# WideFeatherWing.net
KiCad netlist of a schematic drawn in EAGLE
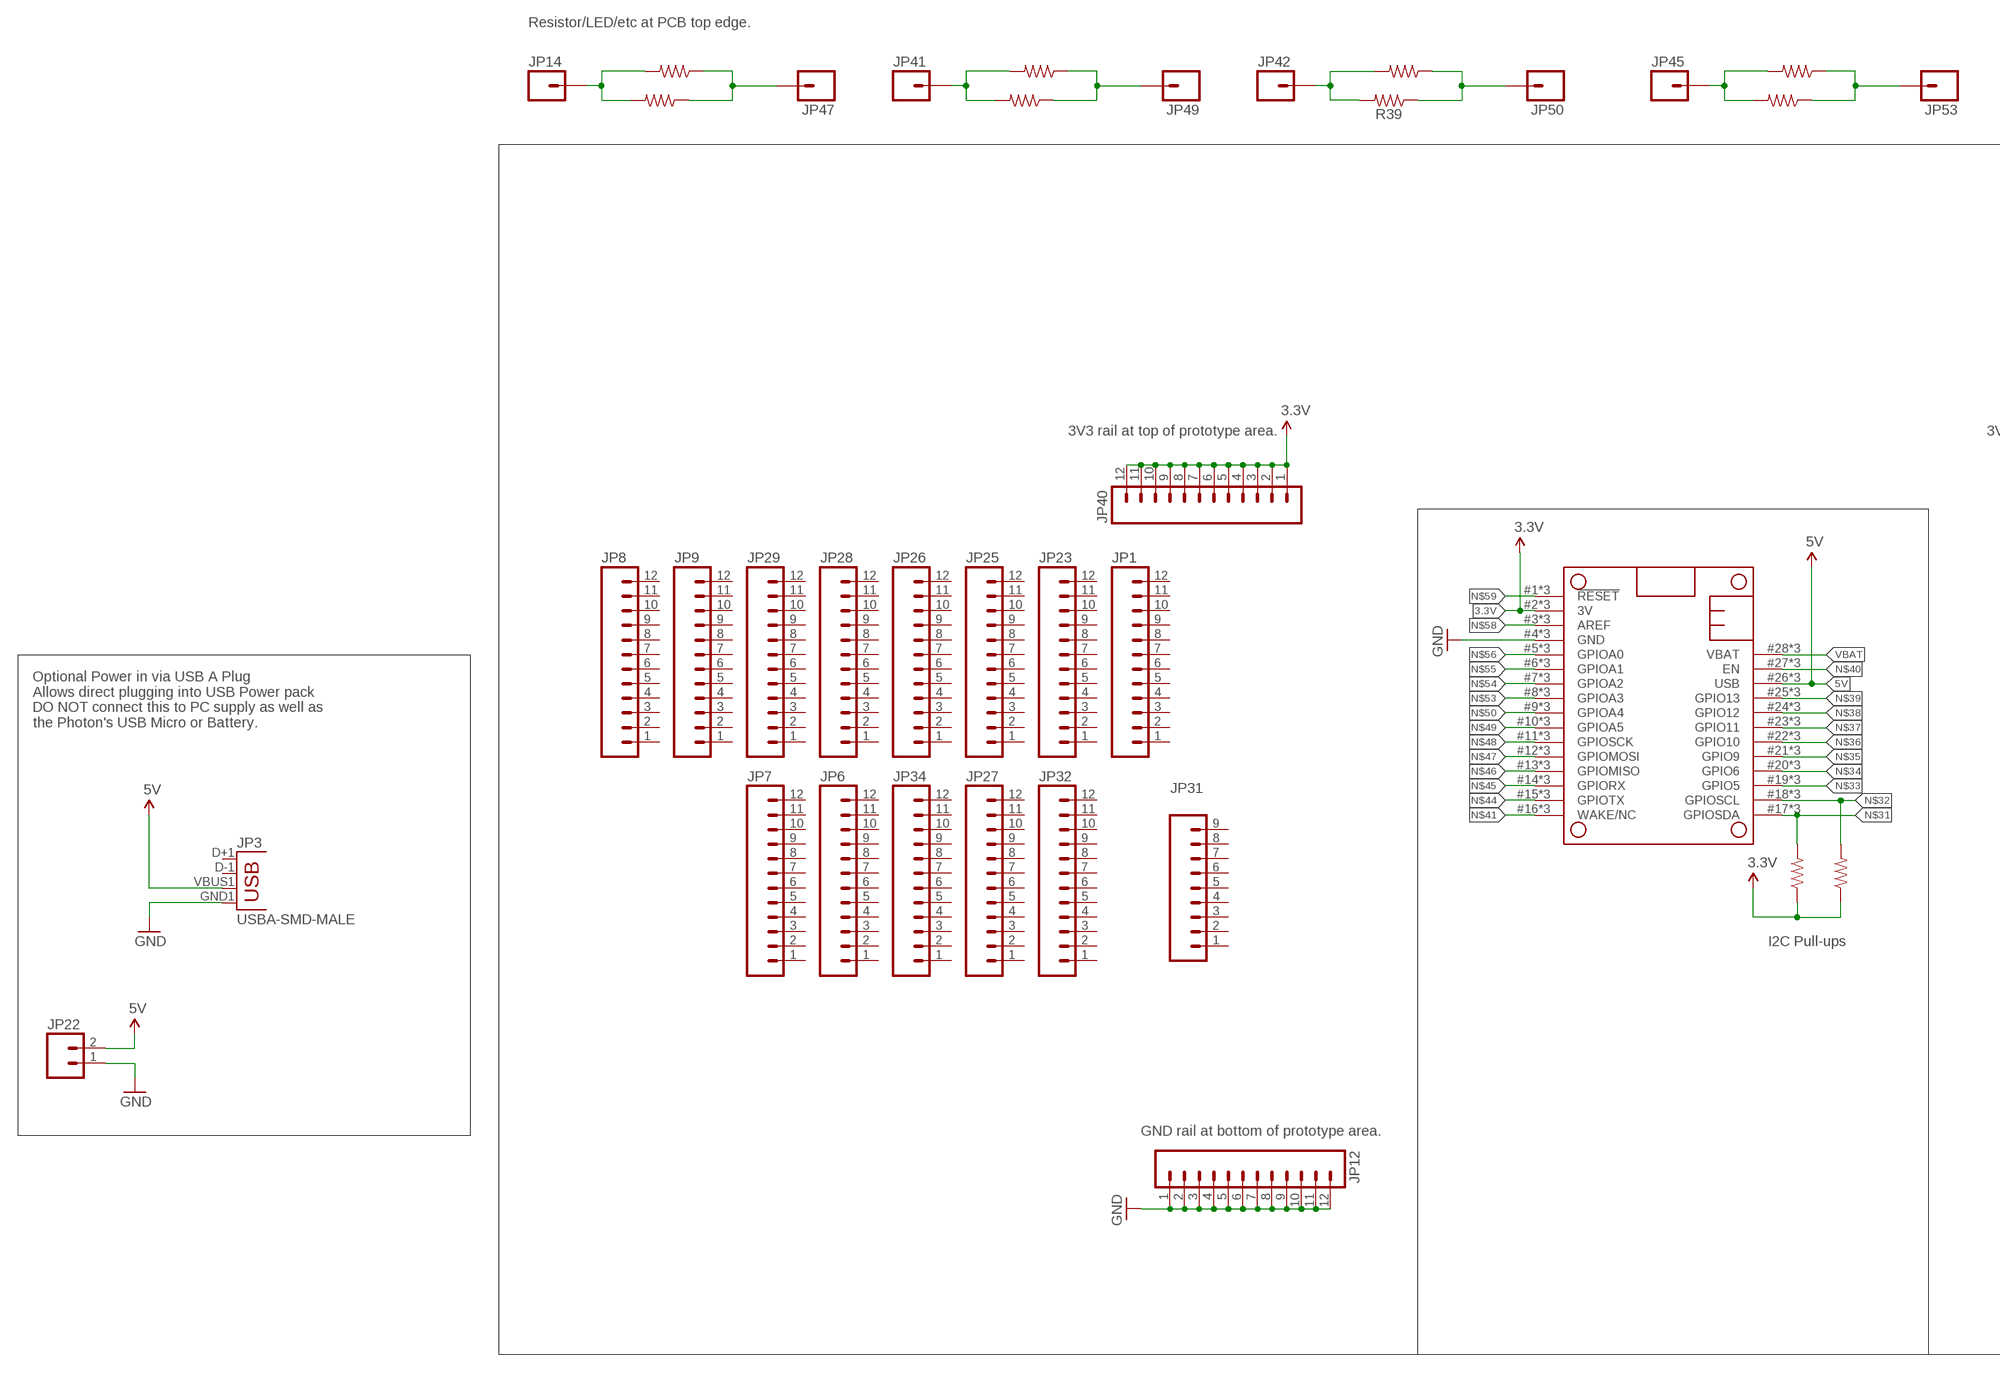
[diagram p0: schematic, sheet 1, part 1 of 2]
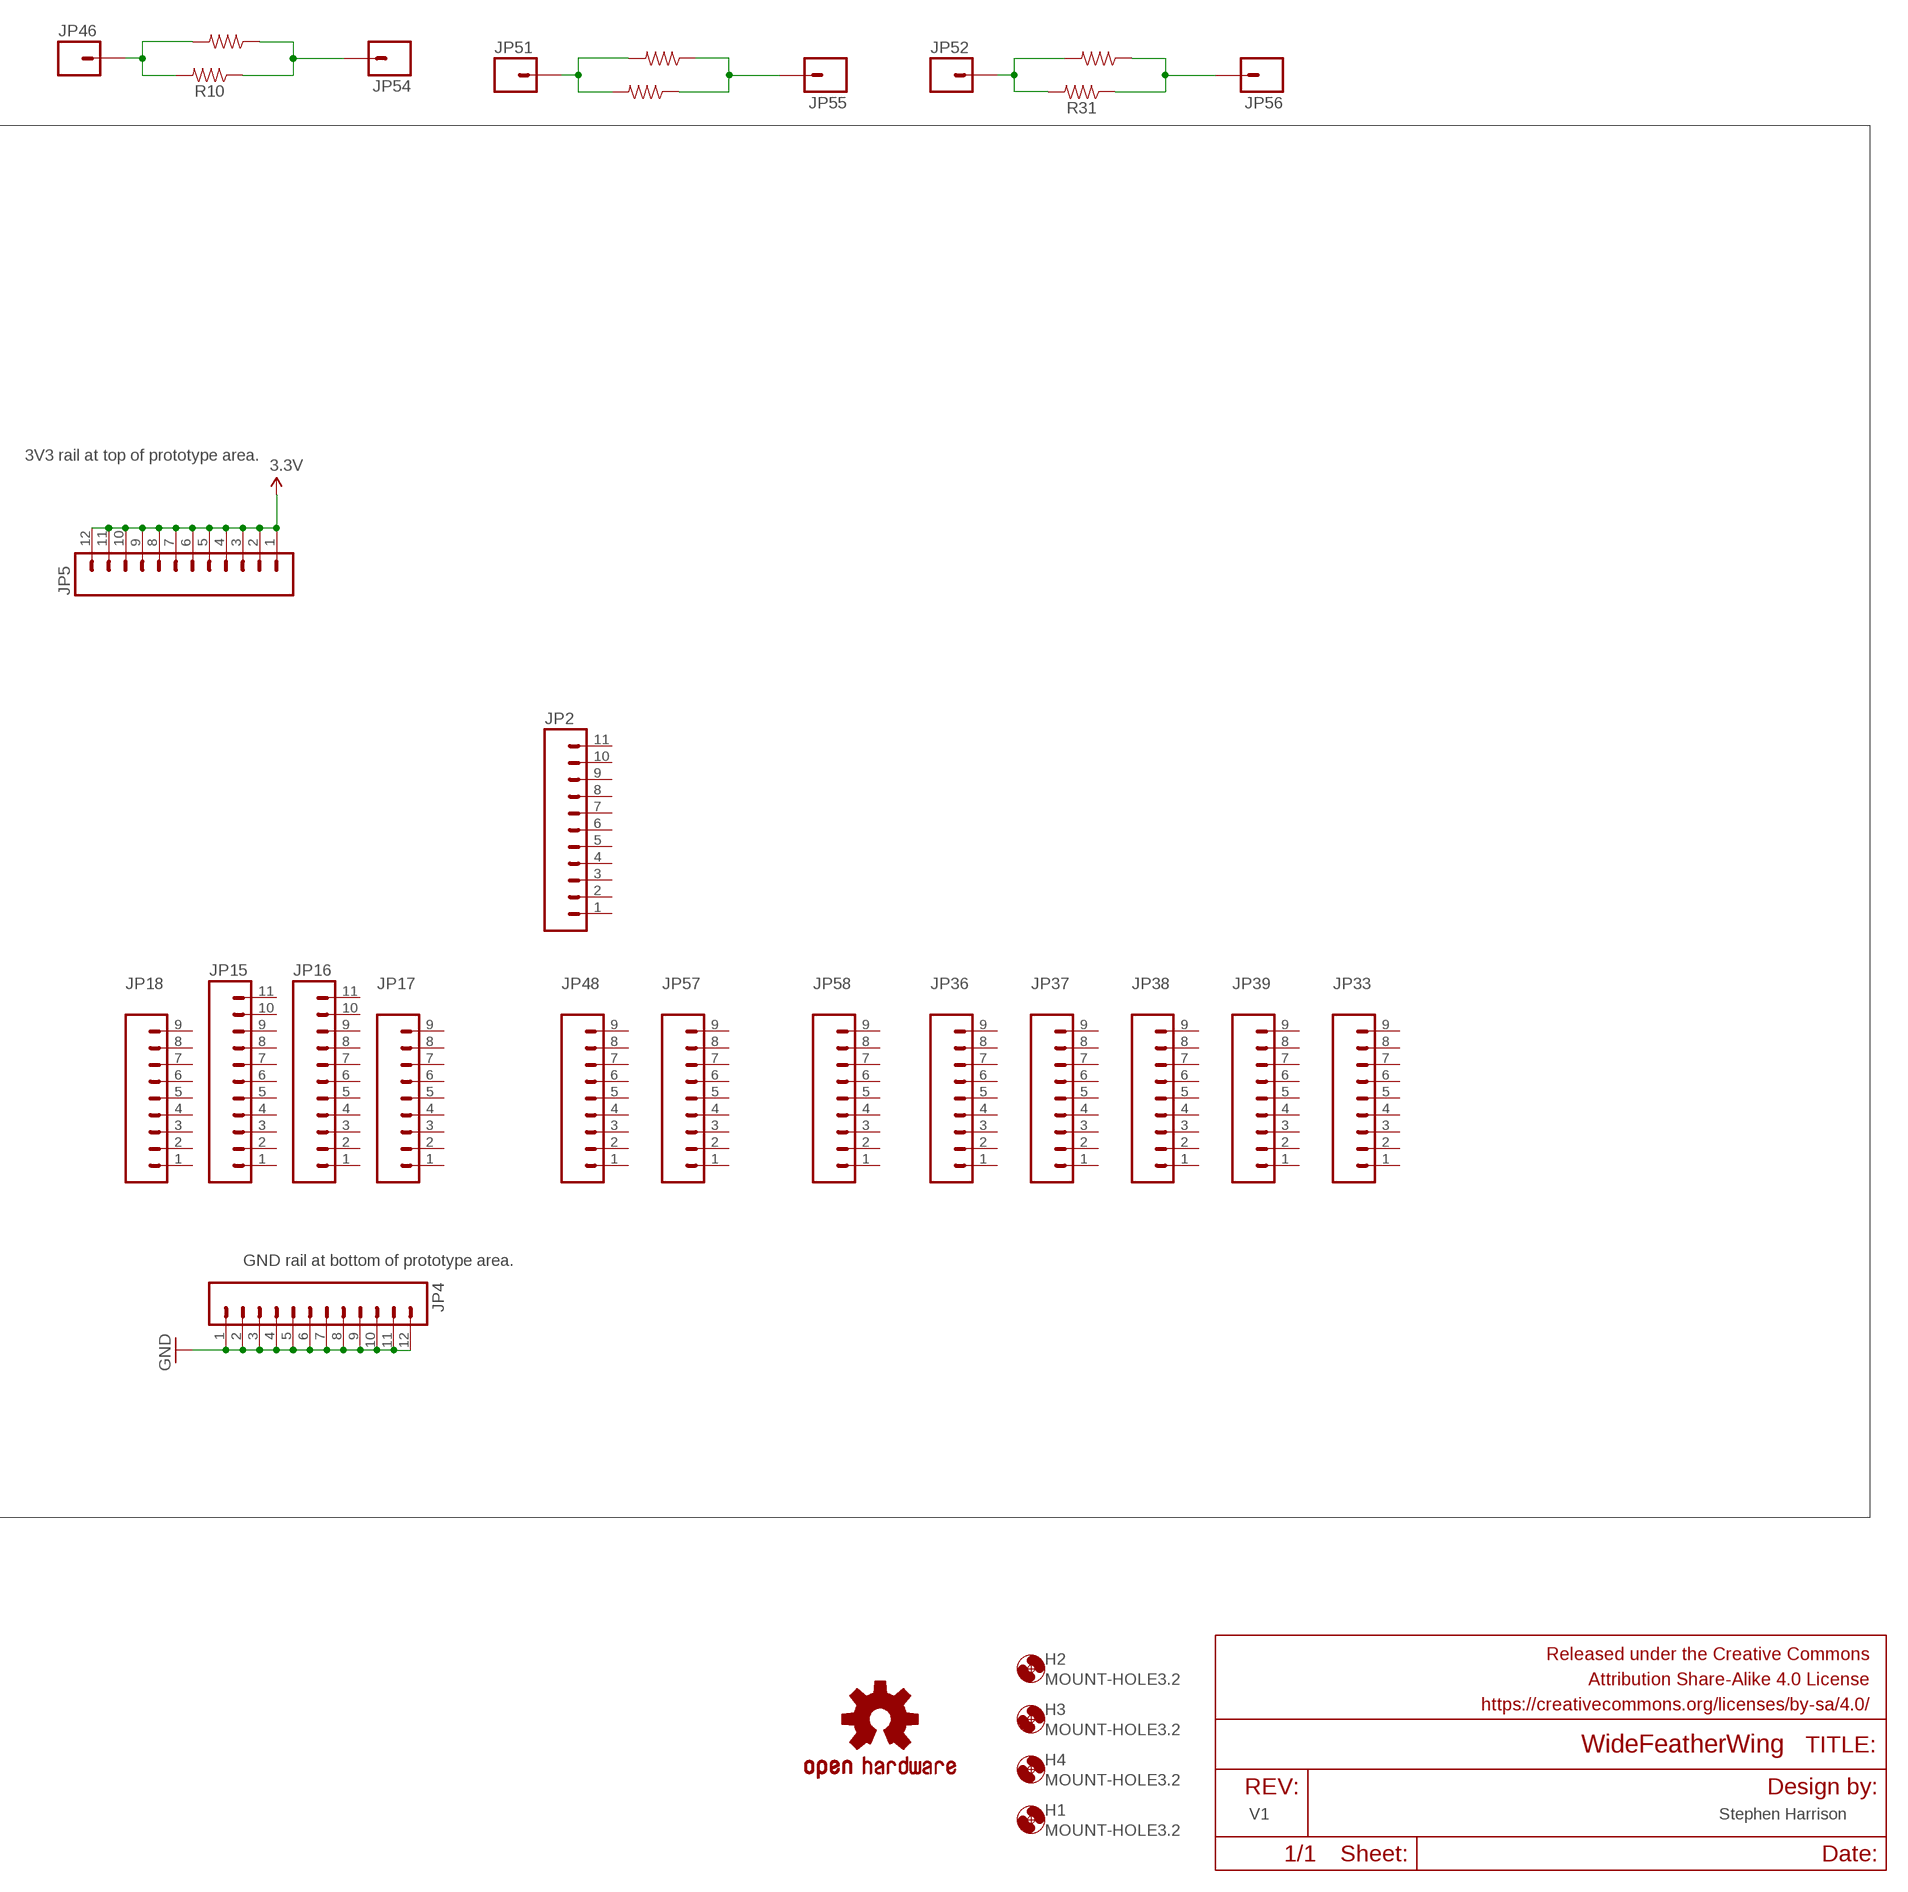
[diagram p1: schematic, sheet 1, part 2 of 2]

(export (version "E")
  (design (tool "Eeschema 10.0.6"))
  (components
    (comp (ref "FRAME1")
      (value "FRAME-LEDGER")
      (footprint "eagle-import:CREATIVE_COMMONS")
      (libsource (lib "eagle-import") (part "FRAME-LEDGER"))
    )
    (comp (ref "H1")
      (value "MOUNT-HOLE3.2")
      (footprint "eagle-import:3,2")
      (libsource (lib "eagle-import") (part "MOUNT-HOLE3.2"))
    )
    (comp (ref "H2")
      (value "MOUNT-HOLE3.2")
      (footprint "eagle-import:3,2")
      (libsource (lib "eagle-import") (part "MOUNT-HOLE3.2"))
    )
    (comp (ref "H3")
      (value "MOUNT-HOLE3.2")
      (footprint "eagle-import:3,2")
      (libsource (lib "eagle-import") (part "MOUNT-HOLE3.2"))
    )
    (comp (ref "H4")
      (value "MOUNT-HOLE3.2")
      (footprint "eagle-import:3,2")
      (libsource (lib "eagle-import") (part "MOUNT-HOLE3.2"))
    )
    (comp (ref "JP1")
      (value "M12NO_SILK")
      (footprint "eagle-import:1X12_NO_SILK")
      (libsource (lib "eagle-import") (part "M12NO_SILK"))
    )
    (comp (ref "JP2")
      (value "M111X11_NO_SILK")
      (footprint "eagle-import:1X11_NO_SILK")
      (libsource (lib "eagle-import") (part "M111X11_NO_SILK"))
    )
    (comp (ref "JP3")
      (value "USBA-SMD-MALE")
      (footprint "eagle-import:USB-A-SMT-MALE")
      (libsource (lib "eagle-import") (part "USBA-SMD-MALE"))
    )
    (comp (ref "JP4")
      (value "M12PTH")
      (footprint "eagle-import:1X12")
      (libsource (lib "eagle-import") (part "M12PTH"))
    )
    (comp (ref "JP5")
      (value "M12PTH")
      (footprint "eagle-import:1X12")
      (libsource (lib "eagle-import") (part "M12PTH"))
    )
    (comp (ref "JP6")
      (value "M12NO_SILK")
      (footprint "eagle-import:1X12_NO_SILK")
      (libsource (lib "eagle-import") (part "M12NO_SILK"))
    )
    (comp (ref "JP7")
      (value "M12NO_SILK")
      (footprint "eagle-import:1X12_NO_SILK")
      (libsource (lib "eagle-import") (part "M12NO_SILK"))
    )
    (comp (ref "JP8")
      (value "M12NO_SILK")
      (footprint "eagle-import:1X12_NO_SILK")
      (libsource (lib "eagle-import") (part "M12NO_SILK"))
    )
    (comp (ref "JP9")
      (value "M12NO_SILK")
      (footprint "eagle-import:1X12_NO_SILK")
      (libsource (lib "eagle-import") (part "M12NO_SILK"))
    )
    (comp (ref "JP12")
      (value "M12PTH")
      (footprint "eagle-import:1X12")
      (libsource (lib "eagle-import") (part "M12PTH"))
    )
    (comp (ref "JP14")
      (value "M01PTH")
      (footprint "eagle-import:1X01")
      (libsource (lib "eagle-import") (part "M01PTH"))
    )
    (comp (ref "JP15")
      (value "M111X11_NO_SILK")
      (footprint "eagle-import:1X11_NO_SILK")
      (libsource (lib "eagle-import") (part "M111X11_NO_SILK"))
    )
    (comp (ref "JP16")
      (value "M111X11_NO_SILK")
      (footprint "eagle-import:1X11_NO_SILK")
      (libsource (lib "eagle-import") (part "M111X11_NO_SILK"))
    )
    (comp (ref "JP17")
      (value "M09NO_SILK")
      (footprint "eagle-import:1X09_NO_SILK")
      (libsource (lib "eagle-import") (part "M09NO_SILK"))
    )
    (comp (ref "JP18")
      (value "M09NO_SILK")
      (footprint "eagle-import:1X09_NO_SILK")
      (libsource (lib "eagle-import") (part "M09NO_SILK"))
    )
    (comp (ref "JP22")
      (value "M021X02_NO_SILK")
      (footprint "eagle-import:1X02_NO_SILK")
      (libsource (lib "eagle-import") (part "M021X02_NO_SILK"))
    )
    (comp (ref "JP23")
      (value "M12NO_SILK")
      (footprint "eagle-import:1X12_NO_SILK")
      (libsource (lib "eagle-import") (part "M12NO_SILK"))
    )
    (comp (ref "JP25")
      (value "M12NO_SILK")
      (footprint "eagle-import:1X12_NO_SILK")
      (libsource (lib "eagle-import") (part "M12NO_SILK"))
    )
    (comp (ref "JP26")
      (value "M12NO_SILK")
      (footprint "eagle-import:1X12_NO_SILK")
      (libsource (lib "eagle-import") (part "M12NO_SILK"))
    )
    (comp (ref "JP27")
      (value "M12NO_SILK")
      (footprint "eagle-import:1X12_NO_SILK")
      (libsource (lib "eagle-import") (part "M12NO_SILK"))
    )
    (comp (ref "JP28")
      (value "M12NO_SILK")
      (footprint "eagle-import:1X12_NO_SILK")
      (libsource (lib "eagle-import") (part "M12NO_SILK"))
    )
    (comp (ref "JP29")
      (value "M12NO_SILK")
      (footprint "eagle-import:1X12_NO_SILK")
      (libsource (lib "eagle-import") (part "M12NO_SILK"))
    )
    (comp (ref "JP31")
      (value "M09NO_SILK")
      (footprint "eagle-import:1X09_NO_SILK")
      (libsource (lib "eagle-import") (part "M09NO_SILK"))
    )
    (comp (ref "JP32")
      (value "M12NO_SILK")
      (footprint "eagle-import:1X12_NO_SILK")
      (libsource (lib "eagle-import") (part "M12NO_SILK"))
    )
    (comp (ref "JP33")
      (value "M09NO_SILK")
      (footprint "eagle-import:1X09_NO_SILK")
      (libsource (lib "eagle-import") (part "M09NO_SILK"))
    )
    (comp (ref "JP34")
      (value "M12NO_SILK")
      (footprint "eagle-import:1X12_NO_SILK")
      (libsource (lib "eagle-import") (part "M12NO_SILK"))
    )
    (comp (ref "JP36")
      (value "M09NO_SILK")
      (footprint "eagle-import:1X09_NO_SILK")
      (libsource (lib "eagle-import") (part "M09NO_SILK"))
    )
    (comp (ref "JP37")
      (value "M09NO_SILK")
      (footprint "eagle-import:1X09_NO_SILK")
      (libsource (lib "eagle-import") (part "M09NO_SILK"))
    )
    (comp (ref "JP38")
      (value "M09NO_SILK")
      (footprint "eagle-import:1X09_NO_SILK")
      (libsource (lib "eagle-import") (part "M09NO_SILK"))
    )
    (comp (ref "JP39")
      (value "M09NO_SILK")
      (footprint "eagle-import:1X09_NO_SILK")
      (libsource (lib "eagle-import") (part "M09NO_SILK"))
    )
    (comp (ref "JP40")
      (value "M12PTH")
      (footprint "eagle-import:1X12")
      (libsource (lib "eagle-import") (part "M12PTH"))
    )
    (comp (ref "JP41")
      (value "M01PTH")
      (footprint "eagle-import:1X01")
      (libsource (lib "eagle-import") (part "M01PTH"))
    )
    (comp (ref "JP42")
      (value "M01PTH")
      (footprint "eagle-import:1X01")
      (libsource (lib "eagle-import") (part "M01PTH"))
    )
    (comp (ref "JP45")
      (value "M01PTH")
      (footprint "eagle-import:1X01")
      (libsource (lib "eagle-import") (part "M01PTH"))
    )
    (comp (ref "JP46")
      (value "M01PTH")
      (footprint "eagle-import:1X01")
      (libsource (lib "eagle-import") (part "M01PTH"))
    )
    (comp (ref "JP47")
      (value "M01PTH")
      (footprint "eagle-import:1X01")
      (libsource (lib "eagle-import") (part "M01PTH"))
    )
    (comp (ref "JP48")
      (value "M09NO_SILK")
      (footprint "eagle-import:1X09_NO_SILK")
      (libsource (lib "eagle-import") (part "M09NO_SILK"))
    )
    (comp (ref "JP49")
      (value "M01PTH")
      (footprint "eagle-import:1X01")
      (libsource (lib "eagle-import") (part "M01PTH"))
    )
    (comp (ref "JP50")
      (value "M01PTH")
      (footprint "eagle-import:1X01")
      (libsource (lib "eagle-import") (part "M01PTH"))
    )
    (comp (ref "JP51")
      (value "M01PTH")
      (footprint "eagle-import:1X01")
      (libsource (lib "eagle-import") (part "M01PTH"))
    )
    (comp (ref "JP52")
      (value "M01PTH")
      (footprint "eagle-import:1X01")
      (libsource (lib "eagle-import") (part "M01PTH"))
    )
    (comp (ref "JP53")
      (value "M01PTH")
      (footprint "eagle-import:1X01")
      (libsource (lib "eagle-import") (part "M01PTH"))
    )
    (comp (ref "JP54")
      (value "M01PTH")
      (footprint "eagle-import:1X01")
      (libsource (lib "eagle-import") (part "M01PTH"))
    )
    (comp (ref "JP55")
      (value "M01PTH")
      (footprint "eagle-import:1X01")
      (libsource (lib "eagle-import") (part "M01PTH"))
    )
    (comp (ref "JP56")
      (value "M01PTH")
      (footprint "eagle-import:1X01")
      (libsource (lib "eagle-import") (part "M01PTH"))
    )
    (comp (ref "JP57")
      (value "M09NO_SILK")
      (footprint "eagle-import:1X09_NO_SILK")
      (libsource (lib "eagle-import") (part "M09NO_SILK"))
    )
    (comp (ref "JP58")
      (value "M09NO_SILK")
      (footprint "eagle-import:1X09_NO_SILK")
      (libsource (lib "eagle-import") (part "M09NO_SILK"))
    )
    (comp (ref "LOGO1")
      (value "OSHW-LOGOM")
      (footprint "eagle-import:OSHW-LOGO-M")
      (libsource (lib "eagle-import") (part "OSHW-LOGOM"))
    )
    (comp (ref "MS1")
      (value "FEATHERWINGFEATHEWING_BREAKOUT")
      (footprint "eagle-import:FEATHERWING_BREAKOUT")
      (libsource (lib "eagle-import") (part "FEATHERWINGFEATHEWING_BREAKOUT"))
    )
    (comp (ref "R5")
      (value "RESISTOR1206")
      (footprint "eagle-import:1206")
      (libsource (lib "eagle-import") (part "RESISTOR1206"))
    )
    (comp (ref "R9")
      (value "RESISTOR1206")
      (footprint "eagle-import:1206")
      (libsource (lib "eagle-import") (part "RESISTOR1206"))
    )
    (comp (ref "R10")
      (value "RESISTOR1206")
      (footprint "eagle-import:1206")
      (libsource (lib "eagle-import") (part "RESISTOR1206"))
    )
    (comp (ref "R17")
      (value "RESISTOR1206")
      (footprint "eagle-import:1206")
      (libsource (lib "eagle-import") (part "RESISTOR1206"))
    )
    (comp (ref "R24")
      (value "RESISTOR1206")
      (footprint "eagle-import:1206")
      (libsource (lib "eagle-import") (part "RESISTOR1206"))
    )
    (comp (ref "R30")
      (value "RESISTOR1206")
      (footprint "eagle-import:1206")
      (libsource (lib "eagle-import") (part "RESISTOR1206"))
    )
    (comp (ref "R31")
      (value "RESISTOR1206")
      (footprint "eagle-import:1206")
      (libsource (lib "eagle-import") (part "RESISTOR1206"))
    )
    (comp (ref "R32")
      (value "RESISTOR1206")
      (footprint "eagle-import:1206")
      (libsource (lib "eagle-import") (part "RESISTOR1206"))
    )
    (comp (ref "R34")
      (value "RESISTOR1206")
      (footprint "eagle-import:1206")
      (libsource (lib "eagle-import") (part "RESISTOR1206"))
    )
    (comp (ref "R35")
      (value "RESISTOR1206")
      (footprint "eagle-import:1206")
      (libsource (lib "eagle-import") (part "RESISTOR1206"))
    )
    (comp (ref "R36")
      (value "RESISTOR1206")
      (footprint "eagle-import:1206")
      (libsource (lib "eagle-import") (part "RESISTOR1206"))
    )
    (comp (ref "R37")
      (value "RESISTOR1206")
      (footprint "eagle-import:1206")
      (libsource (lib "eagle-import") (part "RESISTOR1206"))
    )
    (comp (ref "R39")
      (value "RESISTOR1206")
      (footprint "eagle-import:1206")
      (libsource (lib "eagle-import") (part "RESISTOR1206"))
    )
    (comp (ref "R40")
      (value "RESISTOR1206")
      (footprint "eagle-import:1206")
      (libsource (lib "eagle-import") (part "RESISTOR1206"))
    )
    (comp (ref "R41")
      (value "RESISTOR1206")
      (footprint "eagle-import:1206")
      (libsource (lib "eagle-import") (part "RESISTOR1206"))
    )
    (comp (ref "R44")
      (value "RESISTOR1206")
      (footprint "eagle-import:1206")
      (libsource (lib "eagle-import") (part "RESISTOR1206"))
    )
  )
  (nets
    (net (code "1") (name "3.3V") (class "Default")
      (node (ref "JP40") (pin "1") (pinfunction "1_1") (pintype "passive"))
      (node (ref "JP40") (pin "10") (pinfunction "10_10") (pintype "passive"))
      (node (ref "JP40") (pin "11") (pinfunction "11_11") (pintype "passive"))
      (node (ref "JP40") (pin "12") (pinfunction "12_12") (pintype "passive"))
      (node (ref "JP40") (pin "2") (pinfunction "2_2") (pintype "passive"))
      (node (ref "JP40") (pin "3") (pinfunction "3_3") (pintype "passive"))
      (node (ref "JP40") (pin "4") (pinfunction "4_4") (pintype "passive"))
      (node (ref "JP40") (pin "5") (pinfunction "5_5") (pintype "passive"))
      (node (ref "JP40") (pin "6") (pinfunction "6_6") (pintype "passive"))
      (node (ref "JP40") (pin "7") (pinfunction "7_7") (pintype "passive"))
      (node (ref "JP40") (pin "8") (pinfunction "8_8") (pintype "passive"))
      (node (ref "JP40") (pin "9") (pinfunction "9_9") (pintype "passive"))
      (node (ref "JP5") (pin "1") (pinfunction "1_1") (pintype "passive"))
      (node (ref "JP5") (pin "10") (pinfunction "10_10") (pintype "passive"))
      (node (ref "JP5") (pin "11") (pinfunction "11_11") (pintype "passive"))
      (node (ref "JP5") (pin "12") (pinfunction "12_12") (pintype "passive"))
      (node (ref "JP5") (pin "2") (pinfunction "2_2") (pintype "passive"))
      (node (ref "JP5") (pin "3") (pinfunction "3_3") (pintype "passive"))
      (node (ref "JP5") (pin "4") (pinfunction "4_4") (pintype "passive"))
      (node (ref "JP5") (pin "5") (pinfunction "5_5") (pintype "passive"))
      (node (ref "JP5") (pin "6") (pinfunction "6_6") (pintype "passive"))
      (node (ref "JP5") (pin "7") (pinfunction "7_7") (pintype "passive"))
      (node (ref "JP5") (pin "8") (pinfunction "8_8") (pintype "passive"))
      (node (ref "JP5") (pin "9") (pinfunction "9_9") (pintype "passive"))
      (node (ref "MS1") (pin "#2") (pinfunction "3V_#2") (pintype "power_in"))
      (node (ref "MS1") (pin "2") (pinfunction "3V_2") (pintype "power_in"))
      (node (ref "MS1") (pin "@2") (pinfunction "3V_@2") (pintype "power_in"))
      (node (ref "R5") (pin "1") (pinfunction "1_1") (pintype "passive"))
      (node (ref "R9") (pin "1") (pinfunction "1_1") (pintype "passive"))
    )
    (net (code "2") (name "5V") (class "Default")
      (node (ref "JP22") (pin "2") (pinfunction "2_2") (pintype "passive"))
      (node (ref "JP3") (pin "VBUS1") (pinfunction "VBUS_VBUS1") (pintype "bidirectional"))
      (node (ref "MS1") (pin "#26") (pinfunction "USB_#26") (pintype "power_in"))
      (node (ref "MS1") (pin "26") (pinfunction "USB_26") (pintype "power_in"))
      (node (ref "MS1") (pin "@26") (pinfunction "USB_@26") (pintype "power_in"))
    )
    (net (code "3") (name "GND") (class "Default")
      (node (ref "JP12") (pin "1") (pinfunction "1_1") (pintype "passive"))
      (node (ref "JP12") (pin "10") (pinfunction "10_10") (pintype "passive"))
      (node (ref "JP12") (pin "11") (pinfunction "11_11") (pintype "passive"))
      (node (ref "JP12") (pin "12") (pinfunction "12_12") (pintype "passive"))
      (node (ref "JP12") (pin "2") (pinfunction "2_2") (pintype "passive"))
      (node (ref "JP12") (pin "3") (pinfunction "3_3") (pintype "passive"))
      (node (ref "JP12") (pin "4") (pinfunction "4_4") (pintype "passive"))
      (node (ref "JP12") (pin "5") (pinfunction "5_5") (pintype "passive"))
      (node (ref "JP12") (pin "6") (pinfunction "6_6") (pintype "passive"))
      (node (ref "JP12") (pin "7") (pinfunction "7_7") (pintype "passive"))
      (node (ref "JP12") (pin "8") (pinfunction "8_8") (pintype "passive"))
      (node (ref "JP12") (pin "9") (pinfunction "9_9") (pintype "passive"))
      (node (ref "JP22") (pin "1") (pinfunction "1_1") (pintype "passive"))
      (node (ref "JP3") (pin "GND1") (pinfunction "GND_GND1") (pintype "bidirectional"))
      (node (ref "JP4") (pin "1") (pinfunction "1_1") (pintype "passive"))
      (node (ref "JP4") (pin "10") (pinfunction "10_10") (pintype "passive"))
      (node (ref "JP4") (pin "11") (pinfunction "11_11") (pintype "passive"))
      (node (ref "JP4") (pin "12") (pinfunction "12_12") (pintype "passive"))
      (node (ref "JP4") (pin "2") (pinfunction "2_2") (pintype "passive"))
      (node (ref "JP4") (pin "3") (pinfunction "3_3") (pintype "passive"))
      (node (ref "JP4") (pin "4") (pinfunction "4_4") (pintype "passive"))
      (node (ref "JP4") (pin "5") (pinfunction "5_5") (pintype "passive"))
      (node (ref "JP4") (pin "6") (pinfunction "6_6") (pintype "passive"))
      (node (ref "JP4") (pin "7") (pinfunction "7_7") (pintype "passive"))
      (node (ref "JP4") (pin "8") (pinfunction "8_8") (pintype "passive"))
      (node (ref "JP4") (pin "9") (pinfunction "9_9") (pintype "passive"))
      (node (ref "MS1") (pin "#4") (pinfunction "GND_#4") (pintype "power_in"))
      (node (ref "MS1") (pin "4") (pinfunction "GND_4") (pintype "power_in"))
      (node (ref "MS1") (pin "@4") (pinfunction "GND_@4") (pintype "power_in"))
    )
    (net (code "4") (name "N$31") (class "Default")
      (node (ref "MS1") (pin "#17") (pinfunction "GPIOSDA_#17") (pintype "bidirectional"))
      (node (ref "MS1") (pin "17") (pinfunction "GPIOSDA_17") (pintype "bidirectional"))
      (node (ref "MS1") (pin "@17") (pinfunction "GPIOSDA_@17") (pintype "bidirectional"))
      (node (ref "R5") (pin "2") (pinfunction "2_2") (pintype "passive"))
    )
    (net (code "5") (name "N$32") (class "Default")
      (node (ref "MS1") (pin "#18") (pinfunction "GPIOSCL_#18") (pintype "bidirectional"))
      (node (ref "MS1") (pin "18") (pinfunction "GPIOSCL_18") (pintype "bidirectional"))
      (node (ref "MS1") (pin "@!8") (pinfunction "GPIOSCL_@!8") (pintype "bidirectional"))
      (node (ref "R9") (pin "2") (pinfunction "2_2") (pintype "passive"))
    )
    (net (code "6") (name "N$33") (class "Default")
      (node (ref "MS1") (pin "#19") (pinfunction "GPIO5_#19") (pintype "bidirectional"))
      (node (ref "MS1") (pin "19") (pinfunction "GPIO5_19") (pintype "bidirectional"))
      (node (ref "MS1") (pin "@19") (pinfunction "GPIO5_@19") (pintype "bidirectional"))
    )
    (net (code "7") (name "N$34") (class "Default")
      (node (ref "MS1") (pin "#20") (pinfunction "GPIO6_#20") (pintype "bidirectional"))
      (node (ref "MS1") (pin "20") (pinfunction "GPIO6_20") (pintype "bidirectional"))
      (node (ref "MS1") (pin "@20") (pinfunction "GPIO6_@20") (pintype "bidirectional"))
    )
    (net (code "8") (name "N$35") (class "Default")
      (node (ref "MS1") (pin "#21") (pinfunction "GPIO9_#21") (pintype "bidirectional"))
      (node (ref "MS1") (pin "21") (pinfunction "GPIO9_21") (pintype "bidirectional"))
      (node (ref "MS1") (pin "@21") (pinfunction "GPIO9_@21") (pintype "bidirectional"))
    )
    (net (code "9") (name "N$36") (class "Default")
      (node (ref "MS1") (pin "#22") (pinfunction "GPIO10_#22") (pintype "bidirectional"))
      (node (ref "MS1") (pin "22") (pinfunction "GPIO10_22") (pintype "bidirectional"))
      (node (ref "MS1") (pin "@22") (pinfunction "GPIO10_@22") (pintype "bidirectional"))
    )
    (net (code "10") (name "N$37") (class "Default")
      (node (ref "MS1") (pin "#23") (pinfunction "GPIO11_#23") (pintype "bidirectional"))
      (node (ref "MS1") (pin "23") (pinfunction "GPIO11_23") (pintype "bidirectional"))
      (node (ref "MS1") (pin "@23") (pinfunction "GPIO11_@23") (pintype "bidirectional"))
    )
    (net (code "11") (name "N$38") (class "Default")
      (node (ref "MS1") (pin "#24") (pinfunction "GPIO12_#24") (pintype "bidirectional"))
      (node (ref "MS1") (pin "24") (pinfunction "GPIO12_24") (pintype "bidirectional"))
      (node (ref "MS1") (pin "@24") (pinfunction "GPIO12_@24") (pintype "bidirectional"))
    )
    (net (code "12") (name "N$39") (class "Default")
      (node (ref "MS1") (pin "#25") (pinfunction "GPIO13_#25") (pintype "bidirectional"))
      (node (ref "MS1") (pin "25") (pinfunction "GPIO13_25") (pintype "bidirectional"))
      (node (ref "MS1") (pin "@25") (pinfunction "GPIO13_@25") (pintype "bidirectional"))
    )
    (net (code "13") (name "N$40") (class "Default")
      (node (ref "MS1") (pin "#27") (pinfunction "EN_#27") (pintype "passive"))
      (node (ref "MS1") (pin "27") (pinfunction "EN_27") (pintype "passive"))
      (node (ref "MS1") (pin "@27") (pinfunction "EN_@27") (pintype "passive"))
    )
    (net (code "14") (name "N$41") (class "Default")
      (node (ref "MS1") (pin "#16") (pinfunction "WAKE/NC_#16") (pintype "passive"))
      (node (ref "MS1") (pin "16") (pinfunction "WAKE/NC_16") (pintype "passive"))
      (node (ref "MS1") (pin "@16") (pinfunction "WAKE/NC_@16") (pintype "passive"))
    )
    (net (code "15") (name "N$44") (class "Default")
      (node (ref "MS1") (pin "#15") (pinfunction "GPIOTX_#15") (pintype "bidirectional"))
      (node (ref "MS1") (pin "15") (pinfunction "GPIOTX_15") (pintype "bidirectional"))
      (node (ref "MS1") (pin "@15") (pinfunction "GPIOTX_@15") (pintype "bidirectional"))
    )
    (net (code "16") (name "N$45") (class "Default")
      (node (ref "MS1") (pin "#14") (pinfunction "GPIORX_#14") (pintype "bidirectional"))
      (node (ref "MS1") (pin "14") (pinfunction "GPIORX_14") (pintype "bidirectional"))
      (node (ref "MS1") (pin "@14") (pinfunction "GPIORX_@14") (pintype "bidirectional"))
    )
    (net (code "17") (name "N$46") (class "Default")
      (node (ref "MS1") (pin "#13") (pinfunction "GPIOMISO_#13") (pintype "bidirectional"))
      (node (ref "MS1") (pin "13") (pinfunction "GPIOMISO_13") (pintype "bidirectional"))
      (node (ref "MS1") (pin "@13") (pinfunction "GPIOMISO_@13") (pintype "bidirectional"))
    )
    (net (code "18") (name "N$47") (class "Default")
      (node (ref "MS1") (pin "#12") (pinfunction "GPIOMOSI_#12") (pintype "bidirectional"))
      (node (ref "MS1") (pin "12") (pinfunction "GPIOMOSI_12") (pintype "bidirectional"))
      (node (ref "MS1") (pin "@12") (pinfunction "GPIOMOSI_@12") (pintype "bidirectional"))
    )
    (net (code "19") (name "N$48") (class "Default")
      (node (ref "MS1") (pin "#11") (pinfunction "GPIOSCK_#11") (pintype "bidirectional"))
      (node (ref "MS1") (pin "11") (pinfunction "GPIOSCK_11") (pintype "bidirectional"))
      (node (ref "MS1") (pin "@11") (pinfunction "GPIOSCK_@11") (pintype "bidirectional"))
    )
    (net (code "20") (name "N$49") (class "Default")
      (node (ref "MS1") (pin "#10") (pinfunction "GPIOA5_#10") (pintype "bidirectional"))
      (node (ref "MS1") (pin "10") (pinfunction "GPIOA5_10") (pintype "bidirectional"))
      (node (ref "MS1") (pin "@10") (pinfunction "GPIOA5_@10") (pintype "bidirectional"))
    )
    (net (code "21") (name "N$50") (class "Default")
      (node (ref "MS1") (pin "#9") (pinfunction "GPIOA4_#9") (pintype "bidirectional"))
      (node (ref "MS1") (pin "9") (pinfunction "GPIOA4_9") (pintype "bidirectional"))
      (node (ref "MS1") (pin "@9") (pinfunction "GPIOA4_@9") (pintype "bidirectional"))
    )
    (net (code "22") (name "N$53") (class "Default")
      (node (ref "MS1") (pin "#8") (pinfunction "GPIOA3_#8") (pintype "bidirectional"))
      (node (ref "MS1") (pin "8") (pinfunction "GPIOA3_8") (pintype "bidirectional"))
      (node (ref "MS1") (pin "@8") (pinfunction "GPIOA3_@8") (pintype "bidirectional"))
    )
    (net (code "23") (name "N$54") (class "Default")
      (node (ref "MS1") (pin "#7") (pinfunction "GPIOA2_#7") (pintype "bidirectional"))
      (node (ref "MS1") (pin "7") (pinfunction "GPIOA2_7") (pintype "bidirectional"))
      (node (ref "MS1") (pin "@7") (pinfunction "GPIOA2_@7") (pintype "bidirectional"))
    )
    (net (code "24") (name "N$55") (class "Default")
      (node (ref "MS1") (pin "#6") (pinfunction "GPIOA1_#6") (pintype "bidirectional"))
      (node (ref "MS1") (pin "6") (pinfunction "GPIOA1_6") (pintype "bidirectional"))
      (node (ref "MS1") (pin "@6") (pinfunction "GPIOA1_@6") (pintype "bidirectional"))
    )
    (net (code "25") (name "N$56") (class "Default")
      (node (ref "MS1") (pin "#5") (pinfunction "GPIOA0_#5") (pintype "bidirectional"))
      (node (ref "MS1") (pin "5") (pinfunction "GPIOA0_5") (pintype "bidirectional"))
      (node (ref "MS1") (pin "@5") (pinfunction "GPIOA0_@5") (pintype "bidirectional"))
    )
    (net (code "26") (name "N$58") (class "Default")
      (node (ref "MS1") (pin "#3") (pinfunction "AREF_#3") (pintype "passive"))
      (node (ref "MS1") (pin "3") (pinfunction "AREF_3") (pintype "passive"))
      (node (ref "MS1") (pin "@3") (pinfunction "AREF_@3") (pintype "passive"))
    )
    (net (code "27") (name "N$59") (class "Default")
      (node (ref "MS1") (pin "#1") (pinfunction "~{RESET}_#1") (pintype "input"))
      (node (ref "MS1") (pin "1") (pinfunction "~{RESET}_1") (pintype "input"))
      (node (ref "MS1") (pin "@1") (pinfunction "~{RESET}_@1") (pintype "input"))
    )
    (net (code "28") (name "Net-(JP14-Pad1)") (class "Default")
      (node (ref "JP14") (pin "1") (pinfunction "1_1") (pintype "passive"))
      (node (ref "R34") (pin "2") (pinfunction "2_2") (pintype "passive"))
      (node (ref "R35") (pin "2") (pinfunction "2_2") (pintype "passive"))
    )
    (net (code "29") (name "Net-(JP41-Pad1)") (class "Default")
      (node (ref "JP41") (pin "1") (pinfunction "1_1") (pintype "passive"))
      (node (ref "R40") (pin "2") (pinfunction "2_2") (pintype "passive"))
      (node (ref "R41") (pin "2") (pinfunction "2_2") (pintype "passive"))
    )
    (net (code "30") (name "Net-(JP42-Pad1)") (class "Default")
      (node (ref "JP42") (pin "1") (pinfunction "1_1") (pintype "passive"))
      (node (ref "R39") (pin "2") (pinfunction "2_2") (pintype "passive"))
      (node (ref "R44") (pin "2") (pinfunction "2_2") (pintype "passive"))
    )
    (net (code "31") (name "Net-(JP45-Pad1)") (class "Default")
      (node (ref "JP45") (pin "1") (pinfunction "1_1") (pintype "passive"))
      (node (ref "R17") (pin "2") (pinfunction "2_2") (pintype "passive"))
      (node (ref "R24") (pin "2") (pinfunction "2_2") (pintype "passive"))
    )
    (net (code "32") (name "Net-(JP46-Pad1)") (class "Default")
      (node (ref "JP46") (pin "1") (pinfunction "1_1") (pintype "passive"))
      (node (ref "R10") (pin "2") (pinfunction "2_2") (pintype "passive"))
      (node (ref "R30") (pin "2") (pinfunction "2_2") (pintype "passive"))
    )
    (net (code "33") (name "Net-(JP47-Pad1)") (class "Default")
      (node (ref "JP47") (pin "1") (pinfunction "1_1") (pintype "passive"))
      (node (ref "R34") (pin "1") (pinfunction "1_1") (pintype "passive"))
      (node (ref "R35") (pin "1") (pinfunction "1_1") (pintype "passive"))
    )
    (net (code "34") (name "Net-(JP49-Pad1)") (class "Default")
      (node (ref "JP49") (pin "1") (pinfunction "1_1") (pintype "passive"))
      (node (ref "R40") (pin "1") (pinfunction "1_1") (pintype "passive"))
      (node (ref "R41") (pin "1") (pinfunction "1_1") (pintype "passive"))
    )
    (net (code "35") (name "Net-(JP50-Pad1)") (class "Default")
      (node (ref "JP50") (pin "1") (pinfunction "1_1") (pintype "passive"))
      (node (ref "R39") (pin "1") (pinfunction "1_1") (pintype "passive"))
      (node (ref "R44") (pin "1") (pinfunction "1_1") (pintype "passive"))
    )
    (net (code "36") (name "Net-(JP51-Pad1)") (class "Default")
      (node (ref "JP51") (pin "1") (pinfunction "1_1") (pintype "passive"))
      (node (ref "R32") (pin "2") (pinfunction "2_2") (pintype "passive"))
      (node (ref "R36") (pin "2") (pinfunction "2_2") (pintype "passive"))
    )
    (net (code "37") (name "Net-(JP52-Pad1)") (class "Default")
      (node (ref "JP52") (pin "1") (pinfunction "1_1") (pintype "passive"))
      (node (ref "R31") (pin "2") (pinfunction "2_2") (pintype "passive"))
      (node (ref "R37") (pin "2") (pinfunction "2_2") (pintype "passive"))
    )
    (net (code "38") (name "Net-(JP53-Pad1)") (class "Default")
      (node (ref "JP53") (pin "1") (pinfunction "1_1") (pintype "passive"))
      (node (ref "R17") (pin "1") (pinfunction "1_1") (pintype "passive"))
      (node (ref "R24") (pin "1") (pinfunction "1_1") (pintype "passive"))
    )
    (net (code "39") (name "Net-(JP54-Pad1)") (class "Default")
      (node (ref "JP54") (pin "1") (pinfunction "1_1") (pintype "passive"))
      (node (ref "R10") (pin "1") (pinfunction "1_1") (pintype "passive"))
      (node (ref "R30") (pin "1") (pinfunction "1_1") (pintype "passive"))
    )
    (net (code "40") (name "Net-(JP55-Pad1)") (class "Default")
      (node (ref "JP55") (pin "1") (pinfunction "1_1") (pintype "passive"))
      (node (ref "R32") (pin "1") (pinfunction "1_1") (pintype "passive"))
      (node (ref "R36") (pin "1") (pinfunction "1_1") (pintype "passive"))
    )
    (net (code "41") (name "Net-(JP56-Pad1)") (class "Default")
      (node (ref "JP56") (pin "1") (pinfunction "1_1") (pintype "passive"))
      (node (ref "R31") (pin "1") (pinfunction "1_1") (pintype "passive"))
      (node (ref "R37") (pin "1") (pinfunction "1_1") (pintype "passive"))
    )
    (net (code "42") (name "VBAT") (class "Default")
      (node (ref "MS1") (pin "#28") (pinfunction "VBAT_#28") (pintype "power_in"))
      (node (ref "MS1") (pin "28") (pinfunction "VBAT_28") (pintype "power_in"))
      (node (ref "MS1") (pin "@28") (pinfunction "VBAT_@28") (pintype "power_in"))
    )
    (net (code "43") (name "unconnected-(JP1-Pad1)") (class "Default")
      (node (ref "JP1") (pin "1") (pinfunction "1_1") (pintype "passive"))
    )
    (net (code "44") (name "unconnected-(JP1-Pad2)") (class "Default")
      (node (ref "JP1") (pin "2") (pinfunction "2_2") (pintype "passive"))
    )
    (net (code "45") (name "unconnected-(JP1-Pad3)") (class "Default")
      (node (ref "JP1") (pin "3") (pinfunction "3_3") (pintype "passive"))
    )
    (net (code "46") (name "unconnected-(JP1-Pad4)") (class "Default")
      (node (ref "JP1") (pin "4") (pinfunction "4_4") (pintype "passive"))
    )
    (net (code "47") (name "unconnected-(JP1-Pad5)") (class "Default")
      (node (ref "JP1") (pin "5") (pinfunction "5_5") (pintype "passive"))
    )
    (net (code "48") (name "unconnected-(JP1-Pad6)") (class "Default")
      (node (ref "JP1") (pin "6") (pinfunction "6_6") (pintype "passive"))
    )
    (net (code "49") (name "unconnected-(JP1-Pad7)") (class "Default")
      (node (ref "JP1") (pin "7") (pinfunction "7_7") (pintype "passive"))
    )
    (net (code "50") (name "unconnected-(JP1-Pad8)") (class "Default")
      (node (ref "JP1") (pin "8") (pinfunction "8_8") (pintype "passive"))
    )
    (net (code "51") (name "unconnected-(JP1-Pad9)") (class "Default")
      (node (ref "JP1") (pin "9") (pinfunction "9_9") (pintype "passive"))
    )
    (net (code "52") (name "unconnected-(JP1-Pad10)") (class "Default")
      (node (ref "JP1") (pin "10") (pinfunction "10_10") (pintype "passive"))
    )
    (net (code "53") (name "unconnected-(JP1-Pad11)") (class "Default")
      (node (ref "JP1") (pin "11") (pinfunction "11_11") (pintype "passive"))
    )
    (net (code "54") (name "unconnected-(JP1-Pad12)") (class "Default")
      (node (ref "JP1") (pin "12") (pinfunction "12_12") (pintype "passive"))
    )
    (net (code "55") (name "unconnected-(JP2-Pad1)") (class "Default")
      (node (ref "JP2") (pin "1") (pinfunction "1_1") (pintype "passive"))
    )
    (net (code "56") (name "unconnected-(JP2-Pad2)") (class "Default")
      (node (ref "JP2") (pin "2") (pinfunction "2_2") (pintype "passive"))
    )
    (net (code "57") (name "unconnected-(JP2-Pad3)") (class "Default")
      (node (ref "JP2") (pin "3") (pinfunction "3_3") (pintype "passive"))
    )
    (net (code "58") (name "unconnected-(JP2-Pad4)") (class "Default")
      (node (ref "JP2") (pin "4") (pinfunction "4_4") (pintype "passive"))
    )
    (net (code "59") (name "unconnected-(JP2-Pad5)") (class "Default")
      (node (ref "JP2") (pin "5") (pinfunction "5_5") (pintype "passive"))
    )
    (net (code "60") (name "unconnected-(JP2-Pad6)") (class "Default")
      (node (ref "JP2") (pin "6") (pinfunction "6_6") (pintype "passive"))
    )
    (net (code "61") (name "unconnected-(JP2-Pad7)") (class "Default")
      (node (ref "JP2") (pin "7") (pinfunction "7_7") (pintype "passive"))
    )
    (net (code "62") (name "unconnected-(JP2-Pad8)") (class "Default")
      (node (ref "JP2") (pin "8") (pinfunction "8_8") (pintype "passive"))
    )
    (net (code "63") (name "unconnected-(JP2-Pad9)") (class "Default")
      (node (ref "JP2") (pin "9") (pinfunction "9_9") (pintype "passive"))
    )
    (net (code "64") (name "unconnected-(JP2-Pad10)") (class "Default")
      (node (ref "JP2") (pin "10") (pinfunction "10_10") (pintype "passive"))
    )
    (net (code "65") (name "unconnected-(JP2-Pad11)") (class "Default")
      (node (ref "JP2") (pin "11") (pinfunction "11_11") (pintype "passive"))
    )
    (net (code "66") (name "unconnected-(JP3-D+-PadD+1)") (class "Default")
      (node (ref "JP3") (pin "D+1") (pinfunction "D+_D+1") (pintype "bidirectional"))
    )
    (net (code "67") (name "unconnected-(JP3-D--PadD-1)") (class "Default")
      (node (ref "JP3") (pin "D-1") (pinfunction "D-_D-1") (pintype "bidirectional"))
    )
    (net (code "68") (name "unconnected-(JP6-Pad1)") (class "Default")
      (node (ref "JP6") (pin "1") (pinfunction "1_1") (pintype "passive"))
    )
    (net (code "69") (name "unconnected-(JP6-Pad2)") (class "Default")
      (node (ref "JP6") (pin "2") (pinfunction "2_2") (pintype "passive"))
    )
    (net (code "70") (name "unconnected-(JP6-Pad3)") (class "Default")
      (node (ref "JP6") (pin "3") (pinfunction "3_3") (pintype "passive"))
    )
    (net (code "71") (name "unconnected-(JP6-Pad4)") (class "Default")
      (node (ref "JP6") (pin "4") (pinfunction "4_4") (pintype "passive"))
    )
    (net (code "72") (name "unconnected-(JP6-Pad5)") (class "Default")
      (node (ref "JP6") (pin "5") (pinfunction "5_5") (pintype "passive"))
    )
    (net (code "73") (name "unconnected-(JP6-Pad6)") (class "Default")
      (node (ref "JP6") (pin "6") (pinfunction "6_6") (pintype "passive"))
    )
    (net (code "74") (name "unconnected-(JP6-Pad7)") (class "Default")
      (node (ref "JP6") (pin "7") (pinfunction "7_7") (pintype "passive"))
    )
    (net (code "75") (name "unconnected-(JP6-Pad8)") (class "Default")
      (node (ref "JP6") (pin "8") (pinfunction "8_8") (pintype "passive"))
    )
    (net (code "76") (name "unconnected-(JP6-Pad9)") (class "Default")
      (node (ref "JP6") (pin "9") (pinfunction "9_9") (pintype "passive"))
    )
    (net (code "77") (name "unconnected-(JP6-Pad10)") (class "Default")
      (node (ref "JP6") (pin "10") (pinfunction "10_10") (pintype "passive"))
    )
    (net (code "78") (name "unconnected-(JP6-Pad11)") (class "Default")
      (node (ref "JP6") (pin "11") (pinfunction "11_11") (pintype "passive"))
    )
    (net (code "79") (name "unconnected-(JP6-Pad12)") (class "Default")
      (node (ref "JP6") (pin "12") (pinfunction "12_12") (pintype "passive"))
    )
    (net (code "80") (name "unconnected-(JP7-Pad1)") (class "Default")
      (node (ref "JP7") (pin "1") (pinfunction "1_1") (pintype "passive"))
    )
    (net (code "81") (name "unconnected-(JP7-Pad2)") (class "Default")
      (node (ref "JP7") (pin "2") (pinfunction "2_2") (pintype "passive"))
    )
    (net (code "82") (name "unconnected-(JP7-Pad3)") (class "Default")
      (node (ref "JP7") (pin "3") (pinfunction "3_3") (pintype "passive"))
    )
    (net (code "83") (name "unconnected-(JP7-Pad4)") (class "Default")
      (node (ref "JP7") (pin "4") (pinfunction "4_4") (pintype "passive"))
    )
    (net (code "84") (name "unconnected-(JP7-Pad5)") (class "Default")
      (node (ref "JP7") (pin "5") (pinfunction "5_5") (pintype "passive"))
    )
    (net (code "85") (name "unconnected-(JP7-Pad6)") (class "Default")
      (node (ref "JP7") (pin "6") (pinfunction "6_6") (pintype "passive"))
    )
    (net (code "86") (name "unconnected-(JP7-Pad7)") (class "Default")
      (node (ref "JP7") (pin "7") (pinfunction "7_7") (pintype "passive"))
    )
    (net (code "87") (name "unconnected-(JP7-Pad8)") (class "Default")
      (node (ref "JP7") (pin "8") (pinfunction "8_8") (pintype "passive"))
    )
    (net (code "88") (name "unconnected-(JP7-Pad9)") (class "Default")
      (node (ref "JP7") (pin "9") (pinfunction "9_9") (pintype "passive"))
    )
    (net (code "89") (name "unconnected-(JP7-Pad10)") (class "Default")
      (node (ref "JP7") (pin "10") (pinfunction "10_10") (pintype "passive"))
    )
    (net (code "90") (name "unconnected-(JP7-Pad11)") (class "Default")
      (node (ref "JP7") (pin "11") (pinfunction "11_11") (pintype "passive"))
    )
    (net (code "91") (name "unconnected-(JP7-Pad12)") (class "Default")
      (node (ref "JP7") (pin "12") (pinfunction "12_12") (pintype "passive"))
    )
    (net (code "92") (name "unconnected-(JP8-Pad1)") (class "Default")
      (node (ref "JP8") (pin "1") (pinfunction "1_1") (pintype "passive"))
    )
    (net (code "93") (name "unconnected-(JP8-Pad2)") (class "Default")
      (node (ref "JP8") (pin "2") (pinfunction "2_2") (pintype "passive"))
    )
    (net (code "94") (name "unconnected-(JP8-Pad3)") (class "Default")
      (node (ref "JP8") (pin "3") (pinfunction "3_3") (pintype "passive"))
    )
    (net (code "95") (name "unconnected-(JP8-Pad4)") (class "Default")
      (node (ref "JP8") (pin "4") (pinfunction "4_4") (pintype "passive"))
    )
    (net (code "96") (name "unconnected-(JP8-Pad5)") (class "Default")
      (node (ref "JP8") (pin "5") (pinfunction "5_5") (pintype "passive"))
    )
    (net (code "97") (name "unconnected-(JP8-Pad6)") (class "Default")
      (node (ref "JP8") (pin "6") (pinfunction "6_6") (pintype "passive"))
    )
    (net (code "98") (name "unconnected-(JP8-Pad7)") (class "Default")
      (node (ref "JP8") (pin "7") (pinfunction "7_7") (pintype "passive"))
    )
    (net (code "99") (name "unconnected-(JP8-Pad8)") (class "Default")
      (node (ref "JP8") (pin "8") (pinfunction "8_8") (pintype "passive"))
    )
    (net (code "100") (name "unconnected-(JP8-Pad9)") (class "Default")
      (node (ref "JP8") (pin "9") (pinfunction "9_9") (pintype "passive"))
    )
    (net (code "101") (name "unconnected-(JP8-Pad10)") (class "Default")
      (node (ref "JP8") (pin "10") (pinfunction "10_10") (pintype "passive"))
    )
    (net (code "102") (name "unconnected-(JP8-Pad11)") (class "Default")
      (node (ref "JP8") (pin "11") (pinfunction "11_11") (pintype "passive"))
    )
    (net (code "103") (name "unconnected-(JP8-Pad12)") (class "Default")
      (node (ref "JP8") (pin "12") (pinfunction "12_12") (pintype "passive"))
    )
    (net (code "104") (name "unconnected-(JP9-Pad1)") (class "Default")
      (node (ref "JP9") (pin "1") (pinfunction "1_1") (pintype "passive"))
    )
    (net (code "105") (name "unconnected-(JP9-Pad2)") (class "Default")
      (node (ref "JP9") (pin "2") (pinfunction "2_2") (pintype "passive"))
    )
    (net (code "106") (name "unconnected-(JP9-Pad3)") (class "Default")
      (node (ref "JP9") (pin "3") (pinfunction "3_3") (pintype "passive"))
    )
    (net (code "107") (name "unconnected-(JP9-Pad4)") (class "Default")
      (node (ref "JP9") (pin "4") (pinfunction "4_4") (pintype "passive"))
    )
    (net (code "108") (name "unconnected-(JP9-Pad5)") (class "Default")
      (node (ref "JP9") (pin "5") (pinfunction "5_5") (pintype "passive"))
    )
    (net (code "109") (name "unconnected-(JP9-Pad6)") (class "Default")
      (node (ref "JP9") (pin "6") (pinfunction "6_6") (pintype "passive"))
    )
    (net (code "110") (name "unconnected-(JP9-Pad7)") (class "Default")
      (node (ref "JP9") (pin "7") (pinfunction "7_7") (pintype "passive"))
    )
    (net (code "111") (name "unconnected-(JP9-Pad8)") (class "Default")
      (node (ref "JP9") (pin "8") (pinfunction "8_8") (pintype "passive"))
    )
    (net (code "112") (name "unconnected-(JP9-Pad9)") (class "Default")
      (node (ref "JP9") (pin "9") (pinfunction "9_9") (pintype "passive"))
    )
    (net (code "113") (name "unconnected-(JP9-Pad10)") (class "Default")
      (node (ref "JP9") (pin "10") (pinfunction "10_10") (pintype "passive"))
    )
    (net (code "114") (name "unconnected-(JP9-Pad11)") (class "Default")
      (node (ref "JP9") (pin "11") (pinfunction "11_11") (pintype "passive"))
    )
    (net (code "115") (name "unconnected-(JP9-Pad12)") (class "Default")
      (node (ref "JP9") (pin "12") (pinfunction "12_12") (pintype "passive"))
    )
    (net (code "116") (name "unconnected-(JP15-Pad1)") (class "Default")
      (node (ref "JP15") (pin "1") (pinfunction "1_1") (pintype "passive"))
    )
    (net (code "117") (name "unconnected-(JP15-Pad2)") (class "Default")
      (node (ref "JP15") (pin "2") (pinfunction "2_2") (pintype "passive"))
    )
    (net (code "118") (name "unconnected-(JP15-Pad3)") (class "Default")
      (node (ref "JP15") (pin "3") (pinfunction "3_3") (pintype "passive"))
    )
    (net (code "119") (name "unconnected-(JP15-Pad4)") (class "Default")
      (node (ref "JP15") (pin "4") (pinfunction "4_4") (pintype "passive"))
    )
    (net (code "120") (name "unconnected-(JP15-Pad5)") (class "Default")
      (node (ref "JP15") (pin "5") (pinfunction "5_5") (pintype "passive"))
    )
    (net (code "121") (name "unconnected-(JP15-Pad6)") (class "Default")
      (node (ref "JP15") (pin "6") (pinfunction "6_6") (pintype "passive"))
    )
    (net (code "122") (name "unconnected-(JP15-Pad7)") (class "Default")
      (node (ref "JP15") (pin "7") (pinfunction "7_7") (pintype "passive"))
    )
    (net (code "123") (name "unconnected-(JP15-Pad8)") (class "Default")
      (node (ref "JP15") (pin "8") (pinfunction "8_8") (pintype "passive"))
    )
    (net (code "124") (name "unconnected-(JP15-Pad9)") (class "Default")
      (node (ref "JP15") (pin "9") (pinfunction "9_9") (pintype "passive"))
    )
    (net (code "125") (name "unconnected-(JP15-Pad10)") (class "Default")
      (node (ref "JP15") (pin "10") (pinfunction "10_10") (pintype "passive"))
    )
    (net (code "126") (name "unconnected-(JP15-Pad11)") (class "Default")
      (node (ref "JP15") (pin "11") (pinfunction "11_11") (pintype "passive"))
    )
    (net (code "127") (name "unconnected-(JP16-Pad1)") (class "Default")
      (node (ref "JP16") (pin "1") (pinfunction "1_1") (pintype "passive"))
    )
    (net (code "128") (name "unconnected-(JP16-Pad2)") (class "Default")
      (node (ref "JP16") (pin "2") (pinfunction "2_2") (pintype "passive"))
    )
    (net (code "129") (name "unconnected-(JP16-Pad3)") (class "Default")
      (node (ref "JP16") (pin "3") (pinfunction "3_3") (pintype "passive"))
    )
    (net (code "130") (name "unconnected-(JP16-Pad4)") (class "Default")
      (node (ref "JP16") (pin "4") (pinfunction "4_4") (pintype "passive"))
    )
    (net (code "131") (name "unconnected-(JP16-Pad5)") (class "Default")
      (node (ref "JP16") (pin "5") (pinfunction "5_5") (pintype "passive"))
    )
    (net (code "132") (name "unconnected-(JP16-Pad6)") (class "Default")
      (node (ref "JP16") (pin "6") (pinfunction "6_6") (pintype "passive"))
    )
    (net (code "133") (name "unconnected-(JP16-Pad7)") (class "Default")
      (node (ref "JP16") (pin "7") (pinfunction "7_7") (pintype "passive"))
    )
    (net (code "134") (name "unconnected-(JP16-Pad8)") (class "Default")
      (node (ref "JP16") (pin "8") (pinfunction "8_8") (pintype "passive"))
    )
    (net (code "135") (name "unconnected-(JP16-Pad9)") (class "Default")
      (node (ref "JP16") (pin "9") (pinfunction "9_9") (pintype "passive"))
    )
    (net (code "136") (name "unconnected-(JP16-Pad10)") (class "Default")
      (node (ref "JP16") (pin "10") (pinfunction "10_10") (pintype "passive"))
    )
    (net (code "137") (name "unconnected-(JP16-Pad11)") (class "Default")
      (node (ref "JP16") (pin "11") (pinfunction "11_11") (pintype "passive"))
    )
    (net (code "138") (name "unconnected-(JP17-Pad1)") (class "Default")
      (node (ref "JP17") (pin "1") (pinfunction "1_1") (pintype "passive"))
    )
    (net (code "139") (name "unconnected-(JP17-Pad2)") (class "Default")
      (node (ref "JP17") (pin "2") (pinfunction "2_2") (pintype "passive"))
    )
    (net (code "140") (name "unconnected-(JP17-Pad3)") (class "Default")
      (node (ref "JP17") (pin "3") (pinfunction "3_3") (pintype "passive"))
    )
    (net (code "141") (name "unconnected-(JP17-Pad4)") (class "Default")
      (node (ref "JP17") (pin "4") (pinfunction "4_4") (pintype "passive"))
    )
    (net (code "142") (name "unconnected-(JP17-Pad5)") (class "Default")
      (node (ref "JP17") (pin "5") (pinfunction "5_5") (pintype "passive"))
    )
    (net (code "143") (name "unconnected-(JP17-Pad6)") (class "Default")
      (node (ref "JP17") (pin "6") (pinfunction "6_6") (pintype "passive"))
    )
    (net (code "144") (name "unconnected-(JP17-Pad7)") (class "Default")
      (node (ref "JP17") (pin "7") (pinfunction "7_7") (pintype "passive"))
    )
    (net (code "145") (name "unconnected-(JP17-Pad8)") (class "Default")
      (node (ref "JP17") (pin "8") (pinfunction "8_8") (pintype "passive"))
    )
    (net (code "146") (name "unconnected-(JP17-Pad9)") (class "Default")
      (node (ref "JP17") (pin "9") (pinfunction "9_9") (pintype "passive"))
    )
    (net (code "147") (name "unconnected-(JP18-Pad1)") (class "Default")
      (node (ref "JP18") (pin "1") (pinfunction "1_1") (pintype "passive"))
    )
    (net (code "148") (name "unconnected-(JP18-Pad2)") (class "Default")
      (node (ref "JP18") (pin "2") (pinfunction "2_2") (pintype "passive"))
    )
    (net (code "149") (name "unconnected-(JP18-Pad3)") (class "Default")
      (node (ref "JP18") (pin "3") (pinfunction "3_3") (pintype "passive"))
    )
    (net (code "150") (name "unconnected-(JP18-Pad4)") (class "Default")
      (node (ref "JP18") (pin "4") (pinfunction "4_4") (pintype "passive"))
    )
    (net (code "151") (name "unconnected-(JP18-Pad5)") (class "Default")
      (node (ref "JP18") (pin "5") (pinfunction "5_5") (pintype "passive"))
    )
    (net (code "152") (name "unconnected-(JP18-Pad6)") (class "Default")
      (node (ref "JP18") (pin "6") (pinfunction "6_6") (pintype "passive"))
    )
    (net (code "153") (name "unconnected-(JP18-Pad7)") (class "Default")
      (node (ref "JP18") (pin "7") (pinfunction "7_7") (pintype "passive"))
    )
    (net (code "154") (name "unconnected-(JP18-Pad8)") (class "Default")
      (node (ref "JP18") (pin "8") (pinfunction "8_8") (pintype "passive"))
    )
    (net (code "155") (name "unconnected-(JP18-Pad9)") (class "Default")
      (node (ref "JP18") (pin "9") (pinfunction "9_9") (pintype "passive"))
    )
    (net (code "156") (name "unconnected-(JP23-Pad1)") (class "Default")
      (node (ref "JP23") (pin "1") (pinfunction "1_1") (pintype "passive"))
    )
    (net (code "157") (name "unconnected-(JP23-Pad2)") (class "Default")
      (node (ref "JP23") (pin "2") (pinfunction "2_2") (pintype "passive"))
    )
    (net (code "158") (name "unconnected-(JP23-Pad3)") (class "Default")
      (node (ref "JP23") (pin "3") (pinfunction "3_3") (pintype "passive"))
    )
    (net (code "159") (name "unconnected-(JP23-Pad4)") (class "Default")
      (node (ref "JP23") (pin "4") (pinfunction "4_4") (pintype "passive"))
    )
    (net (code "160") (name "unconnected-(JP23-Pad5)") (class "Default")
      (node (ref "JP23") (pin "5") (pinfunction "5_5") (pintype "passive"))
    )
    (net (code "161") (name "unconnected-(JP23-Pad6)") (class "Default")
      (node (ref "JP23") (pin "6") (pinfunction "6_6") (pintype "passive"))
    )
    (net (code "162") (name "unconnected-(JP23-Pad7)") (class "Default")
      (node (ref "JP23") (pin "7") (pinfunction "7_7") (pintype "passive"))
    )
    (net (code "163") (name "unconnected-(JP23-Pad8)") (class "Default")
      (node (ref "JP23") (pin "8") (pinfunction "8_8") (pintype "passive"))
    )
    (net (code "164") (name "unconnected-(JP23-Pad9)") (class "Default")
      (node (ref "JP23") (pin "9") (pinfunction "9_9") (pintype "passive"))
    )
    (net (code "165") (name "unconnected-(JP23-Pad10)") (class "Default")
      (node (ref "JP23") (pin "10") (pinfunction "10_10") (pintype "passive"))
    )
    (net (code "166") (name "unconnected-(JP23-Pad11)") (class "Default")
      (node (ref "JP23") (pin "11") (pinfunction "11_11") (pintype "passive"))
    )
    (net (code "167") (name "unconnected-(JP23-Pad12)") (class "Default")
      (node (ref "JP23") (pin "12") (pinfunction "12_12") (pintype "passive"))
    )
    (net (code "168") (name "unconnected-(JP25-Pad1)") (class "Default")
      (node (ref "JP25") (pin "1") (pinfunction "1_1") (pintype "passive"))
    )
    (net (code "169") (name "unconnected-(JP25-Pad2)") (class "Default")
      (node (ref "JP25") (pin "2") (pinfunction "2_2") (pintype "passive"))
    )
    (net (code "170") (name "unconnected-(JP25-Pad3)") (class "Default")
      (node (ref "JP25") (pin "3") (pinfunction "3_3") (pintype "passive"))
    )
    (net (code "171") (name "unconnected-(JP25-Pad4)") (class "Default")
      (node (ref "JP25") (pin "4") (pinfunction "4_4") (pintype "passive"))
    )
    (net (code "172") (name "unconnected-(JP25-Pad5)") (class "Default")
      (node (ref "JP25") (pin "5") (pinfunction "5_5") (pintype "passive"))
    )
    (net (code "173") (name "unconnected-(JP25-Pad6)") (class "Default")
      (node (ref "JP25") (pin "6") (pinfunction "6_6") (pintype "passive"))
    )
    (net (code "174") (name "unconnected-(JP25-Pad7)") (class "Default")
      (node (ref "JP25") (pin "7") (pinfunction "7_7") (pintype "passive"))
    )
    (net (code "175") (name "unconnected-(JP25-Pad8)") (class "Default")
      (node (ref "JP25") (pin "8") (pinfunction "8_8") (pintype "passive"))
    )
    (net (code "176") (name "unconnected-(JP25-Pad9)") (class "Default")
      (node (ref "JP25") (pin "9") (pinfunction "9_9") (pintype "passive"))
    )
    (net (code "177") (name "unconnected-(JP25-Pad10)") (class "Default")
      (node (ref "JP25") (pin "10") (pinfunction "10_10") (pintype "passive"))
    )
    (net (code "178") (name "unconnected-(JP25-Pad11)") (class "Default")
      (node (ref "JP25") (pin "11") (pinfunction "11_11") (pintype "passive"))
    )
    (net (code "179") (name "unconnected-(JP25-Pad12)") (class "Default")
      (node (ref "JP25") (pin "12") (pinfunction "12_12") (pintype "passive"))
    )
    (net (code "180") (name "unconnected-(JP26-Pad1)") (class "Default")
      (node (ref "JP26") (pin "1") (pinfunction "1_1") (pintype "passive"))
    )
    (net (code "181") (name "unconnected-(JP26-Pad2)") (class "Default")
      (node (ref "JP26") (pin "2") (pinfunction "2_2") (pintype "passive"))
    )
    (net (code "182") (name "unconnected-(JP26-Pad3)") (class "Default")
      (node (ref "JP26") (pin "3") (pinfunction "3_3") (pintype "passive"))
    )
    (net (code "183") (name "unconnected-(JP26-Pad4)") (class "Default")
      (node (ref "JP26") (pin "4") (pinfunction "4_4") (pintype "passive"))
    )
    (net (code "184") (name "unconnected-(JP26-Pad5)") (class "Default")
      (node (ref "JP26") (pin "5") (pinfunction "5_5") (pintype "passive"))
    )
    (net (code "185") (name "unconnected-(JP26-Pad6)") (class "Default")
      (node (ref "JP26") (pin "6") (pinfunction "6_6") (pintype "passive"))
    )
    (net (code "186") (name "unconnected-(JP26-Pad7)") (class "Default")
      (node (ref "JP26") (pin "7") (pinfunction "7_7") (pintype "passive"))
    )
    (net (code "187") (name "unconnected-(JP26-Pad8)") (class "Default")
      (node (ref "JP26") (pin "8") (pinfunction "8_8") (pintype "passive"))
    )
    (net (code "188") (name "unconnected-(JP26-Pad9)") (class "Default")
      (node (ref "JP26") (pin "9") (pinfunction "9_9") (pintype "passive"))
    )
    (net (code "189") (name "unconnected-(JP26-Pad10)") (class "Default")
      (node (ref "JP26") (pin "10") (pinfunction "10_10") (pintype "passive"))
    )
    (net (code "190") (name "unconnected-(JP26-Pad11)") (class "Default")
      (node (ref "JP26") (pin "11") (pinfunction "11_11") (pintype "passive"))
    )
    (net (code "191") (name "unconnected-(JP26-Pad12)") (class "Default")
      (node (ref "JP26") (pin "12") (pinfunction "12_12") (pintype "passive"))
    )
    (net (code "192") (name "unconnected-(JP27-Pad1)") (class "Default")
      (node (ref "JP27") (pin "1") (pinfunction "1_1") (pintype "passive"))
    )
    (net (code "193") (name "unconnected-(JP27-Pad2)") (class "Default")
      (node (ref "JP27") (pin "2") (pinfunction "2_2") (pintype "passive"))
    )
    (net (code "194") (name "unconnected-(JP27-Pad3)") (class "Default")
      (node (ref "JP27") (pin "3") (pinfunction "3_3") (pintype "passive"))
    )
    (net (code "195") (name "unconnected-(JP27-Pad4)") (class "Default")
      (node (ref "JP27") (pin "4") (pinfunction "4_4") (pintype "passive"))
    )
    (net (code "196") (name "unconnected-(JP27-Pad5)") (class "Default")
      (node (ref "JP27") (pin "5") (pinfunction "5_5") (pintype "passive"))
    )
    (net (code "197") (name "unconnected-(JP27-Pad6)") (class "Default")
      (node (ref "JP27") (pin "6") (pinfunction "6_6") (pintype "passive"))
    )
    (net (code "198") (name "unconnected-(JP27-Pad7)") (class "Default")
      (node (ref "JP27") (pin "7") (pinfunction "7_7") (pintype "passive"))
    )
    (net (code "199") (name "unconnected-(JP27-Pad8)") (class "Default")
      (node (ref "JP27") (pin "8") (pinfunction "8_8") (pintype "passive"))
    )
    (net (code "200") (name "unconnected-(JP27-Pad9)") (class "Default")
      (node (ref "JP27") (pin "9") (pinfunction "9_9") (pintype "passive"))
    )
    (net (code "201") (name "unconnected-(JP27-Pad10)") (class "Default")
      (node (ref "JP27") (pin "10") (pinfunction "10_10") (pintype "passive"))
    )
    (net (code "202") (name "unconnected-(JP27-Pad11)") (class "Default")
      (node (ref "JP27") (pin "11") (pinfunction "11_11") (pintype "passive"))
    )
    (net (code "203") (name "unconnected-(JP27-Pad12)") (class "Default")
      (node (ref "JP27") (pin "12") (pinfunction "12_12") (pintype "passive"))
    )
    (net (code "204") (name "unconnected-(JP28-Pad1)") (class "Default")
      (node (ref "JP28") (pin "1") (pinfunction "1_1") (pintype "passive"))
    )
    (net (code "205") (name "unconnected-(JP28-Pad2)") (class "Default")
      (node (ref "JP28") (pin "2") (pinfunction "2_2") (pintype "passive"))
    )
    (net (code "206") (name "unconnected-(JP28-Pad3)") (class "Default")
      (node (ref "JP28") (pin "3") (pinfunction "3_3") (pintype "passive"))
    )
    (net (code "207") (name "unconnected-(JP28-Pad4)") (class "Default")
      (node (ref "JP28") (pin "4") (pinfunction "4_4") (pintype "passive"))
    )
    (net (code "208") (name "unconnected-(JP28-Pad5)") (class "Default")
      (node (ref "JP28") (pin "5") (pinfunction "5_5") (pintype "passive"))
    )
    (net (code "209") (name "unconnected-(JP28-Pad6)") (class "Default")
      (node (ref "JP28") (pin "6") (pinfunction "6_6") (pintype "passive"))
    )
    (net (code "210") (name "unconnected-(JP28-Pad7)") (class "Default")
      (node (ref "JP28") (pin "7") (pinfunction "7_7") (pintype "passive"))
    )
    (net (code "211") (name "unconnected-(JP28-Pad8)") (class "Default")
      (node (ref "JP28") (pin "8") (pinfunction "8_8") (pintype "passive"))
    )
    (net (code "212") (name "unconnected-(JP28-Pad9)") (class "Default")
      (node (ref "JP28") (pin "9") (pinfunction "9_9") (pintype "passive"))
    )
    (net (code "213") (name "unconnected-(JP28-Pad10)") (class "Default")
      (node (ref "JP28") (pin "10") (pinfunction "10_10") (pintype "passive"))
    )
    (net (code "214") (name "unconnected-(JP28-Pad11)") (class "Default")
      (node (ref "JP28") (pin "11") (pinfunction "11_11") (pintype "passive"))
    )
    (net (code "215") (name "unconnected-(JP28-Pad12)") (class "Default")
      (node (ref "JP28") (pin "12") (pinfunction "12_12") (pintype "passive"))
    )
    (net (code "216") (name "unconnected-(JP29-Pad1)") (class "Default")
      (node (ref "JP29") (pin "1") (pinfunction "1_1") (pintype "passive"))
    )
    (net (code "217") (name "unconnected-(JP29-Pad2)") (class "Default")
      (node (ref "JP29") (pin "2") (pinfunction "2_2") (pintype "passive"))
    )
    (net (code "218") (name "unconnected-(JP29-Pad3)") (class "Default")
      (node (ref "JP29") (pin "3") (pinfunction "3_3") (pintype "passive"))
    )
    (net (code "219") (name "unconnected-(JP29-Pad4)") (class "Default")
      (node (ref "JP29") (pin "4") (pinfunction "4_4") (pintype "passive"))
    )
    (net (code "220") (name "unconnected-(JP29-Pad5)") (class "Default")
      (node (ref "JP29") (pin "5") (pinfunction "5_5") (pintype "passive"))
    )
    (net (code "221") (name "unconnected-(JP29-Pad6)") (class "Default")
      (node (ref "JP29") (pin "6") (pinfunction "6_6") (pintype "passive"))
    )
    (net (code "222") (name "unconnected-(JP29-Pad7)") (class "Default")
      (node (ref "JP29") (pin "7") (pinfunction "7_7") (pintype "passive"))
    )
    (net (code "223") (name "unconnected-(JP29-Pad8)") (class "Default")
      (node (ref "JP29") (pin "8") (pinfunction "8_8") (pintype "passive"))
    )
    (net (code "224") (name "unconnected-(JP29-Pad9)") (class "Default")
      (node (ref "JP29") (pin "9") (pinfunction "9_9") (pintype "passive"))
    )
    (net (code "225") (name "unconnected-(JP29-Pad10)") (class "Default")
      (node (ref "JP29") (pin "10") (pinfunction "10_10") (pintype "passive"))
    )
    (net (code "226") (name "unconnected-(JP29-Pad11)") (class "Default")
      (node (ref "JP29") (pin "11") (pinfunction "11_11") (pintype "passive"))
    )
    (net (code "227") (name "unconnected-(JP29-Pad12)") (class "Default")
      (node (ref "JP29") (pin "12") (pinfunction "12_12") (pintype "passive"))
    )
    (net (code "228") (name "unconnected-(JP31-Pad1)") (class "Default")
      (node (ref "JP31") (pin "1") (pinfunction "1_1") (pintype "passive"))
    )
    (net (code "229") (name "unconnected-(JP31-Pad2)") (class "Default")
      (node (ref "JP31") (pin "2") (pinfunction "2_2") (pintype "passive"))
    )
    (net (code "230") (name "unconnected-(JP31-Pad3)") (class "Default")
      (node (ref "JP31") (pin "3") (pinfunction "3_3") (pintype "passive"))
    )
    (net (code "231") (name "unconnected-(JP31-Pad4)") (class "Default")
      (node (ref "JP31") (pin "4") (pinfunction "4_4") (pintype "passive"))
    )
    (net (code "232") (name "unconnected-(JP31-Pad5)") (class "Default")
      (node (ref "JP31") (pin "5") (pinfunction "5_5") (pintype "passive"))
    )
    (net (code "233") (name "unconnected-(JP31-Pad6)") (class "Default")
      (node (ref "JP31") (pin "6") (pinfunction "6_6") (pintype "passive"))
    )
    (net (code "234") (name "unconnected-(JP31-Pad7)") (class "Default")
      (node (ref "JP31") (pin "7") (pinfunction "7_7") (pintype "passive"))
    )
    (net (code "235") (name "unconnected-(JP31-Pad8)") (class "Default")
      (node (ref "JP31") (pin "8") (pinfunction "8_8") (pintype "passive"))
    )
    (net (code "236") (name "unconnected-(JP31-Pad9)") (class "Default")
      (node (ref "JP31") (pin "9") (pinfunction "9_9") (pintype "passive"))
    )
    (net (code "237") (name "unconnected-(JP32-Pad1)") (class "Default")
      (node (ref "JP32") (pin "1") (pinfunction "1_1") (pintype "passive"))
    )
    (net (code "238") (name "unconnected-(JP32-Pad2)") (class "Default")
      (node (ref "JP32") (pin "2") (pinfunction "2_2") (pintype "passive"))
    )
    (net (code "239") (name "unconnected-(JP32-Pad3)") (class "Default")
      (node (ref "JP32") (pin "3") (pinfunction "3_3") (pintype "passive"))
    )
    (net (code "240") (name "unconnected-(JP32-Pad4)") (class "Default")
      (node (ref "JP32") (pin "4") (pinfunction "4_4") (pintype "passive"))
    )
    (net (code "241") (name "unconnected-(JP32-Pad5)") (class "Default")
      (node (ref "JP32") (pin "5") (pinfunction "5_5") (pintype "passive"))
    )
    (net (code "242") (name "unconnected-(JP32-Pad6)") (class "Default")
      (node (ref "JP32") (pin "6") (pinfunction "6_6") (pintype "passive"))
    )
    (net (code "243") (name "unconnected-(JP32-Pad7)") (class "Default")
      (node (ref "JP32") (pin "7") (pinfunction "7_7") (pintype "passive"))
    )
    (net (code "244") (name "unconnected-(JP32-Pad8)") (class "Default")
      (node (ref "JP32") (pin "8") (pinfunction "8_8") (pintype "passive"))
    )
    (net (code "245") (name "unconnected-(JP32-Pad9)") (class "Default")
      (node (ref "JP32") (pin "9") (pinfunction "9_9") (pintype "passive"))
    )
    (net (code "246") (name "unconnected-(JP32-Pad10)") (class "Default")
      (node (ref "JP32") (pin "10") (pinfunction "10_10") (pintype "passive"))
    )
    (net (code "247") (name "unconnected-(JP32-Pad11)") (class "Default")
      (node (ref "JP32") (pin "11") (pinfunction "11_11") (pintype "passive"))
    )
    (net (code "248") (name "unconnected-(JP32-Pad12)") (class "Default")
      (node (ref "JP32") (pin "12") (pinfunction "12_12") (pintype "passive"))
    )
    (net (code "249") (name "unconnected-(JP33-Pad1)") (class "Default")
      (node (ref "JP33") (pin "1") (pinfunction "1_1") (pintype "passive"))
    )
    (net (code "250") (name "unconnected-(JP33-Pad2)") (class "Default")
      (node (ref "JP33") (pin "2") (pinfunction "2_2") (pintype "passive"))
    )
    (net (code "251") (name "unconnected-(JP33-Pad3)") (class "Default")
      (node (ref "JP33") (pin "3") (pinfunction "3_3") (pintype "passive"))
    )
    (net (code "252") (name "unconnected-(JP33-Pad4)") (class "Default")
      (node (ref "JP33") (pin "4") (pinfunction "4_4") (pintype "passive"))
    )
    (net (code "253") (name "unconnected-(JP33-Pad5)") (class "Default")
      (node (ref "JP33") (pin "5") (pinfunction "5_5") (pintype "passive"))
    )
    (net (code "254") (name "unconnected-(JP33-Pad6)") (class "Default")
      (node (ref "JP33") (pin "6") (pinfunction "6_6") (pintype "passive"))
    )
    (net (code "255") (name "unconnected-(JP33-Pad7)") (class "Default")
      (node (ref "JP33") (pin "7") (pinfunction "7_7") (pintype "passive"))
    )
    (net (code "256") (name "unconnected-(JP33-Pad8)") (class "Default")
      (node (ref "JP33") (pin "8") (pinfunction "8_8") (pintype "passive"))
    )
    (net (code "257") (name "unconnected-(JP33-Pad9)") (class "Default")
      (node (ref "JP33") (pin "9") (pinfunction "9_9") (pintype "passive"))
    )
    (net (code "258") (name "unconnected-(JP34-Pad1)") (class "Default")
      (node (ref "JP34") (pin "1") (pinfunction "1_1") (pintype "passive"))
    )
    (net (code "259") (name "unconnected-(JP34-Pad2)") (class "Default")
      (node (ref "JP34") (pin "2") (pinfunction "2_2") (pintype "passive"))
    )
    (net (code "260") (name "unconnected-(JP34-Pad3)") (class "Default")
      (node (ref "JP34") (pin "3") (pinfunction "3_3") (pintype "passive"))
    )
    (net (code "261") (name "unconnected-(JP34-Pad4)") (class "Default")
      (node (ref "JP34") (pin "4") (pinfunction "4_4") (pintype "passive"))
    )
    (net (code "262") (name "unconnected-(JP34-Pad5)") (class "Default")
      (node (ref "JP34") (pin "5") (pinfunction "5_5") (pintype "passive"))
    )
    (net (code "263") (name "unconnected-(JP34-Pad6)") (class "Default")
      (node (ref "JP34") (pin "6") (pinfunction "6_6") (pintype "passive"))
    )
    (net (code "264") (name "unconnected-(JP34-Pad7)") (class "Default")
      (node (ref "JP34") (pin "7") (pinfunction "7_7") (pintype "passive"))
    )
    (net (code "265") (name "unconnected-(JP34-Pad8)") (class "Default")
      (node (ref "JP34") (pin "8") (pinfunction "8_8") (pintype "passive"))
    )
    (net (code "266") (name "unconnected-(JP34-Pad9)") (class "Default")
      (node (ref "JP34") (pin "9") (pinfunction "9_9") (pintype "passive"))
    )
    (net (code "267") (name "unconnected-(JP34-Pad10)") (class "Default")
      (node (ref "JP34") (pin "10") (pinfunction "10_10") (pintype "passive"))
    )
    (net (code "268") (name "unconnected-(JP34-Pad11)") (class "Default")
      (node (ref "JP34") (pin "11") (pinfunction "11_11") (pintype "passive"))
    )
    (net (code "269") (name "unconnected-(JP34-Pad12)") (class "Default")
      (node (ref "JP34") (pin "12") (pinfunction "12_12") (pintype "passive"))
    )
    (net (code "270") (name "unconnected-(JP36-Pad1)") (class "Default")
      (node (ref "JP36") (pin "1") (pinfunction "1_1") (pintype "passive"))
    )
    (net (code "271") (name "unconnected-(JP36-Pad2)") (class "Default")
      (node (ref "JP36") (pin "2") (pinfunction "2_2") (pintype "passive"))
    )
    (net (code "272") (name "unconnected-(JP36-Pad3)") (class "Default")
      (node (ref "JP36") (pin "3") (pinfunction "3_3") (pintype "passive"))
    )
    (net (code "273") (name "unconnected-(JP36-Pad4)") (class "Default")
      (node (ref "JP36") (pin "4") (pinfunction "4_4") (pintype "passive"))
    )
    (net (code "274") (name "unconnected-(JP36-Pad5)") (class "Default")
      (node (ref "JP36") (pin "5") (pinfunction "5_5") (pintype "passive"))
    )
    (net (code "275") (name "unconnected-(JP36-Pad6)") (class "Default")
      (node (ref "JP36") (pin "6") (pinfunction "6_6") (pintype "passive"))
    )
    (net (code "276") (name "unconnected-(JP36-Pad7)") (class "Default")
      (node (ref "JP36") (pin "7") (pinfunction "7_7") (pintype "passive"))
    )
    (net (code "277") (name "unconnected-(JP36-Pad8)") (class "Default")
      (node (ref "JP36") (pin "8") (pinfunction "8_8") (pintype "passive"))
    )
    (net (code "278") (name "unconnected-(JP36-Pad9)") (class "Default")
      (node (ref "JP36") (pin "9") (pinfunction "9_9") (pintype "passive"))
    )
    (net (code "279") (name "unconnected-(JP37-Pad1)") (class "Default")
      (node (ref "JP37") (pin "1") (pinfunction "1_1") (pintype "passive"))
    )
    (net (code "280") (name "unconnected-(JP37-Pad2)") (class "Default")
      (node (ref "JP37") (pin "2") (pinfunction "2_2") (pintype "passive"))
    )
    (net (code "281") (name "unconnected-(JP37-Pad3)") (class "Default")
      (node (ref "JP37") (pin "3") (pinfunction "3_3") (pintype "passive"))
    )
    (net (code "282") (name "unconnected-(JP37-Pad4)") (class "Default")
      (node (ref "JP37") (pin "4") (pinfunction "4_4") (pintype "passive"))
    )
    (net (code "283") (name "unconnected-(JP37-Pad5)") (class "Default")
      (node (ref "JP37") (pin "5") (pinfunction "5_5") (pintype "passive"))
    )
    (net (code "284") (name "unconnected-(JP37-Pad6)") (class "Default")
      (node (ref "JP37") (pin "6") (pinfunction "6_6") (pintype "passive"))
    )
    (net (code "285") (name "unconnected-(JP37-Pad7)") (class "Default")
      (node (ref "JP37") (pin "7") (pinfunction "7_7") (pintype "passive"))
    )
    (net (code "286") (name "unconnected-(JP37-Pad8)") (class "Default")
      (node (ref "JP37") (pin "8") (pinfunction "8_8") (pintype "passive"))
    )
    (net (code "287") (name "unconnected-(JP37-Pad9)") (class "Default")
      (node (ref "JP37") (pin "9") (pinfunction "9_9") (pintype "passive"))
    )
    (net (code "288") (name "unconnected-(JP38-Pad1)") (class "Default")
      (node (ref "JP38") (pin "1") (pinfunction "1_1") (pintype "passive"))
    )
    (net (code "289") (name "unconnected-(JP38-Pad2)") (class "Default")
      (node (ref "JP38") (pin "2") (pinfunction "2_2") (pintype "passive"))
    )
    (net (code "290") (name "unconnected-(JP38-Pad3)") (class "Default")
      (node (ref "JP38") (pin "3") (pinfunction "3_3") (pintype "passive"))
    )
    (net (code "291") (name "unconnected-(JP38-Pad4)") (class "Default")
      (node (ref "JP38") (pin "4") (pinfunction "4_4") (pintype "passive"))
    )
    (net (code "292") (name "unconnected-(JP38-Pad5)") (class "Default")
      (node (ref "JP38") (pin "5") (pinfunction "5_5") (pintype "passive"))
    )
    (net (code "293") (name "unconnected-(JP38-Pad6)") (class "Default")
      (node (ref "JP38") (pin "6") (pinfunction "6_6") (pintype "passive"))
    )
    (net (code "294") (name "unconnected-(JP38-Pad7)") (class "Default")
      (node (ref "JP38") (pin "7") (pinfunction "7_7") (pintype "passive"))
    )
    (net (code "295") (name "unconnected-(JP38-Pad8)") (class "Default")
      (node (ref "JP38") (pin "8") (pinfunction "8_8") (pintype "passive"))
    )
    (net (code "296") (name "unconnected-(JP38-Pad9)") (class "Default")
      (node (ref "JP38") (pin "9") (pinfunction "9_9") (pintype "passive"))
    )
    (net (code "297") (name "unconnected-(JP39-Pad1)") (class "Default")
      (node (ref "JP39") (pin "1") (pinfunction "1_1") (pintype "passive"))
    )
    (net (code "298") (name "unconnected-(JP39-Pad2)") (class "Default")
      (node (ref "JP39") (pin "2") (pinfunction "2_2") (pintype "passive"))
    )
    (net (code "299") (name "unconnected-(JP39-Pad3)") (class "Default")
      (node (ref "JP39") (pin "3") (pinfunction "3_3") (pintype "passive"))
    )
    (net (code "300") (name "unconnected-(JP39-Pad4)") (class "Default")
      (node (ref "JP39") (pin "4") (pinfunction "4_4") (pintype "passive"))
    )
    (net (code "301") (name "unconnected-(JP39-Pad5)") (class "Default")
      (node (ref "JP39") (pin "5") (pinfunction "5_5") (pintype "passive"))
    )
    (net (code "302") (name "unconnected-(JP39-Pad6)") (class "Default")
      (node (ref "JP39") (pin "6") (pinfunction "6_6") (pintype "passive"))
    )
    (net (code "303") (name "unconnected-(JP39-Pad7)") (class "Default")
      (node (ref "JP39") (pin "7") (pinfunction "7_7") (pintype "passive"))
    )
    (net (code "304") (name "unconnected-(JP39-Pad8)") (class "Default")
      (node (ref "JP39") (pin "8") (pinfunction "8_8") (pintype "passive"))
    )
    (net (code "305") (name "unconnected-(JP39-Pad9)") (class "Default")
      (node (ref "JP39") (pin "9") (pinfunction "9_9") (pintype "passive"))
    )
    (net (code "306") (name "unconnected-(JP48-Pad1)") (class "Default")
      (node (ref "JP48") (pin "1") (pinfunction "1_1") (pintype "passive"))
    )
    (net (code "307") (name "unconnected-(JP48-Pad2)") (class "Default")
      (node (ref "JP48") (pin "2") (pinfunction "2_2") (pintype "passive"))
    )
    (net (code "308") (name "unconnected-(JP48-Pad3)") (class "Default")
      (node (ref "JP48") (pin "3") (pinfunction "3_3") (pintype "passive"))
    )
    (net (code "309") (name "unconnected-(JP48-Pad4)") (class "Default")
      (node (ref "JP48") (pin "4") (pinfunction "4_4") (pintype "passive"))
    )
    (net (code "310") (name "unconnected-(JP48-Pad5)") (class "Default")
      (node (ref "JP48") (pin "5") (pinfunction "5_5") (pintype "passive"))
    )
    (net (code "311") (name "unconnected-(JP48-Pad6)") (class "Default")
      (node (ref "JP48") (pin "6") (pinfunction "6_6") (pintype "passive"))
    )
    (net (code "312") (name "unconnected-(JP48-Pad7)") (class "Default")
      (node (ref "JP48") (pin "7") (pinfunction "7_7") (pintype "passive"))
    )
    (net (code "313") (name "unconnected-(JP48-Pad8)") (class "Default")
      (node (ref "JP48") (pin "8") (pinfunction "8_8") (pintype "passive"))
    )
    (net (code "314") (name "unconnected-(JP48-Pad9)") (class "Default")
      (node (ref "JP48") (pin "9") (pinfunction "9_9") (pintype "passive"))
    )
    (net (code "315") (name "unconnected-(JP57-Pad1)") (class "Default")
      (node (ref "JP57") (pin "1") (pinfunction "1_1") (pintype "passive"))
    )
    (net (code "316") (name "unconnected-(JP57-Pad2)") (class "Default")
      (node (ref "JP57") (pin "2") (pinfunction "2_2") (pintype "passive"))
    )
    (net (code "317") (name "unconnected-(JP57-Pad3)") (class "Default")
      (node (ref "JP57") (pin "3") (pinfunction "3_3") (pintype "passive"))
    )
    (net (code "318") (name "unconnected-(JP57-Pad4)") (class "Default")
      (node (ref "JP57") (pin "4") (pinfunction "4_4") (pintype "passive"))
    )
    (net (code "319") (name "unconnected-(JP57-Pad5)") (class "Default")
      (node (ref "JP57") (pin "5") (pinfunction "5_5") (pintype "passive"))
    )
    (net (code "320") (name "unconnected-(JP57-Pad6)") (class "Default")
      (node (ref "JP57") (pin "6") (pinfunction "6_6") (pintype "passive"))
    )
    (net (code "321") (name "unconnected-(JP57-Pad7)") (class "Default")
      (node (ref "JP57") (pin "7") (pinfunction "7_7") (pintype "passive"))
    )
    (net (code "322") (name "unconnected-(JP57-Pad8)") (class "Default")
      (node (ref "JP57") (pin "8") (pinfunction "8_8") (pintype "passive"))
    )
    (net (code "323") (name "unconnected-(JP57-Pad9)") (class "Default")
      (node (ref "JP57") (pin "9") (pinfunction "9_9") (pintype "passive"))
    )
    (net (code "324") (name "unconnected-(JP58-Pad1)") (class "Default")
      (node (ref "JP58") (pin "1") (pinfunction "1_1") (pintype "passive"))
    )
    (net (code "325") (name "unconnected-(JP58-Pad2)") (class "Default")
      (node (ref "JP58") (pin "2") (pinfunction "2_2") (pintype "passive"))
    )
    (net (code "326") (name "unconnected-(JP58-Pad3)") (class "Default")
      (node (ref "JP58") (pin "3") (pinfunction "3_3") (pintype "passive"))
    )
    (net (code "327") (name "unconnected-(JP58-Pad4)") (class "Default")
      (node (ref "JP58") (pin "4") (pinfunction "4_4") (pintype "passive"))
    )
    (net (code "328") (name "unconnected-(JP58-Pad5)") (class "Default")
      (node (ref "JP58") (pin "5") (pinfunction "5_5") (pintype "passive"))
    )
    (net (code "329") (name "unconnected-(JP58-Pad6)") (class "Default")
      (node (ref "JP58") (pin "6") (pinfunction "6_6") (pintype "passive"))
    )
    (net (code "330") (name "unconnected-(JP58-Pad7)") (class "Default")
      (node (ref "JP58") (pin "7") (pinfunction "7_7") (pintype "passive"))
    )
    (net (code "331") (name "unconnected-(JP58-Pad8)") (class "Default")
      (node (ref "JP58") (pin "8") (pinfunction "8_8") (pintype "passive"))
    )
    (net (code "332") (name "unconnected-(JP58-Pad9)") (class "Default")
      (node (ref "JP58") (pin "9") (pinfunction "9_9") (pintype "passive"))
    )
  )
)
